# PCB.net
KiCad netlist of a schematic drawn in EAGLE
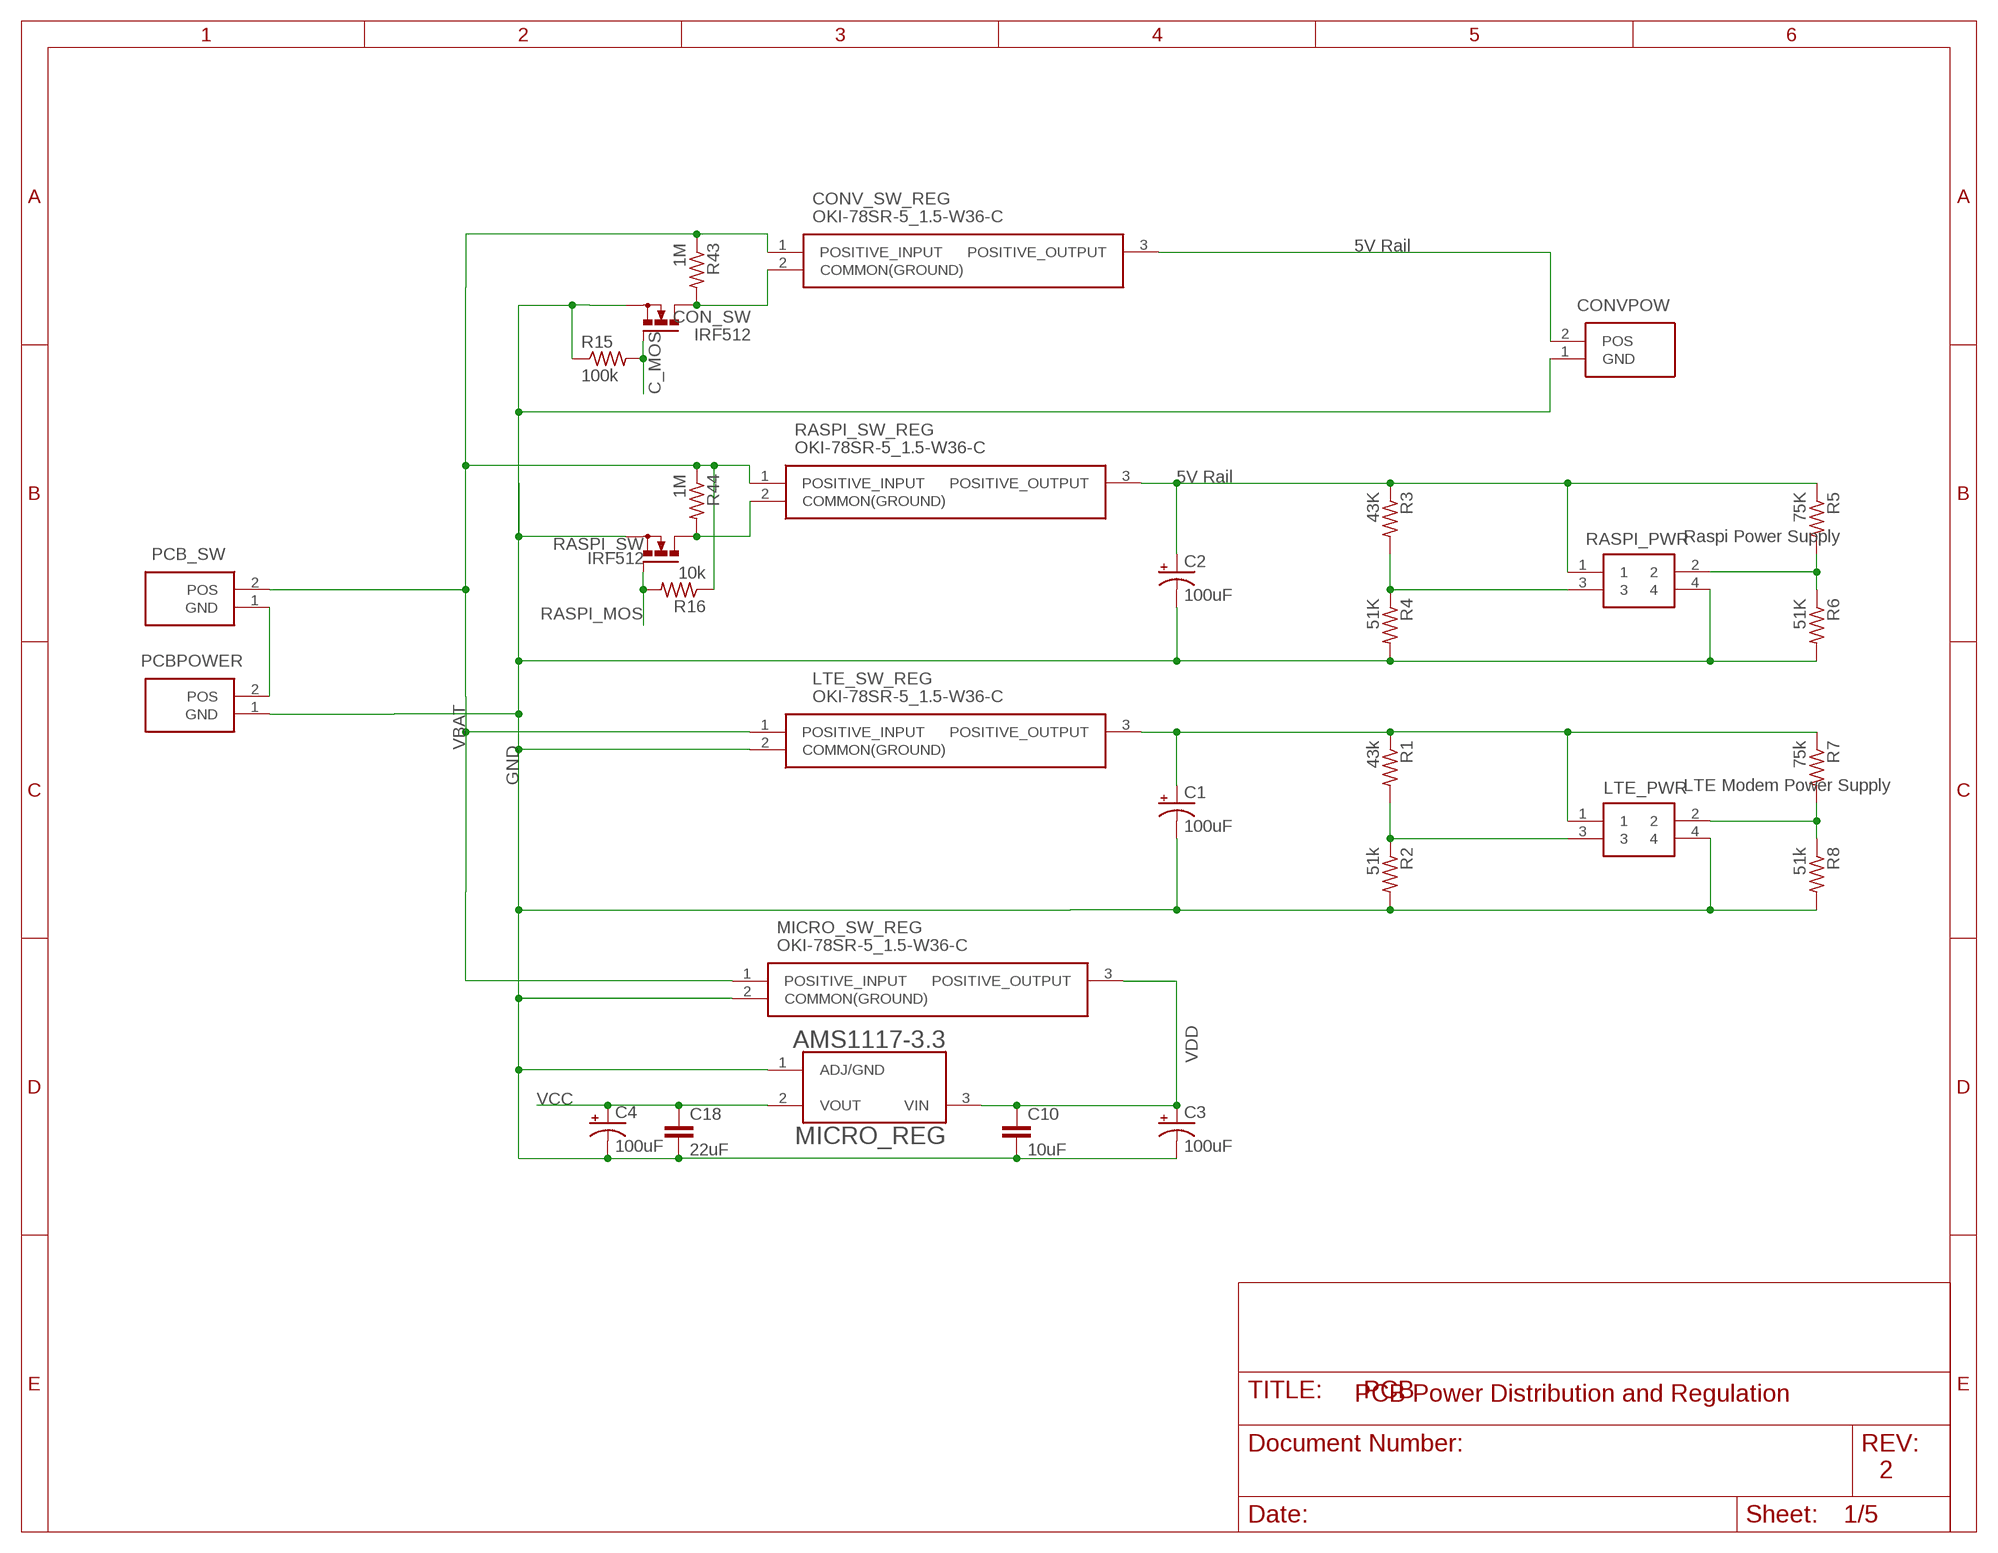
[diagram p0: schematic, sheet 1]
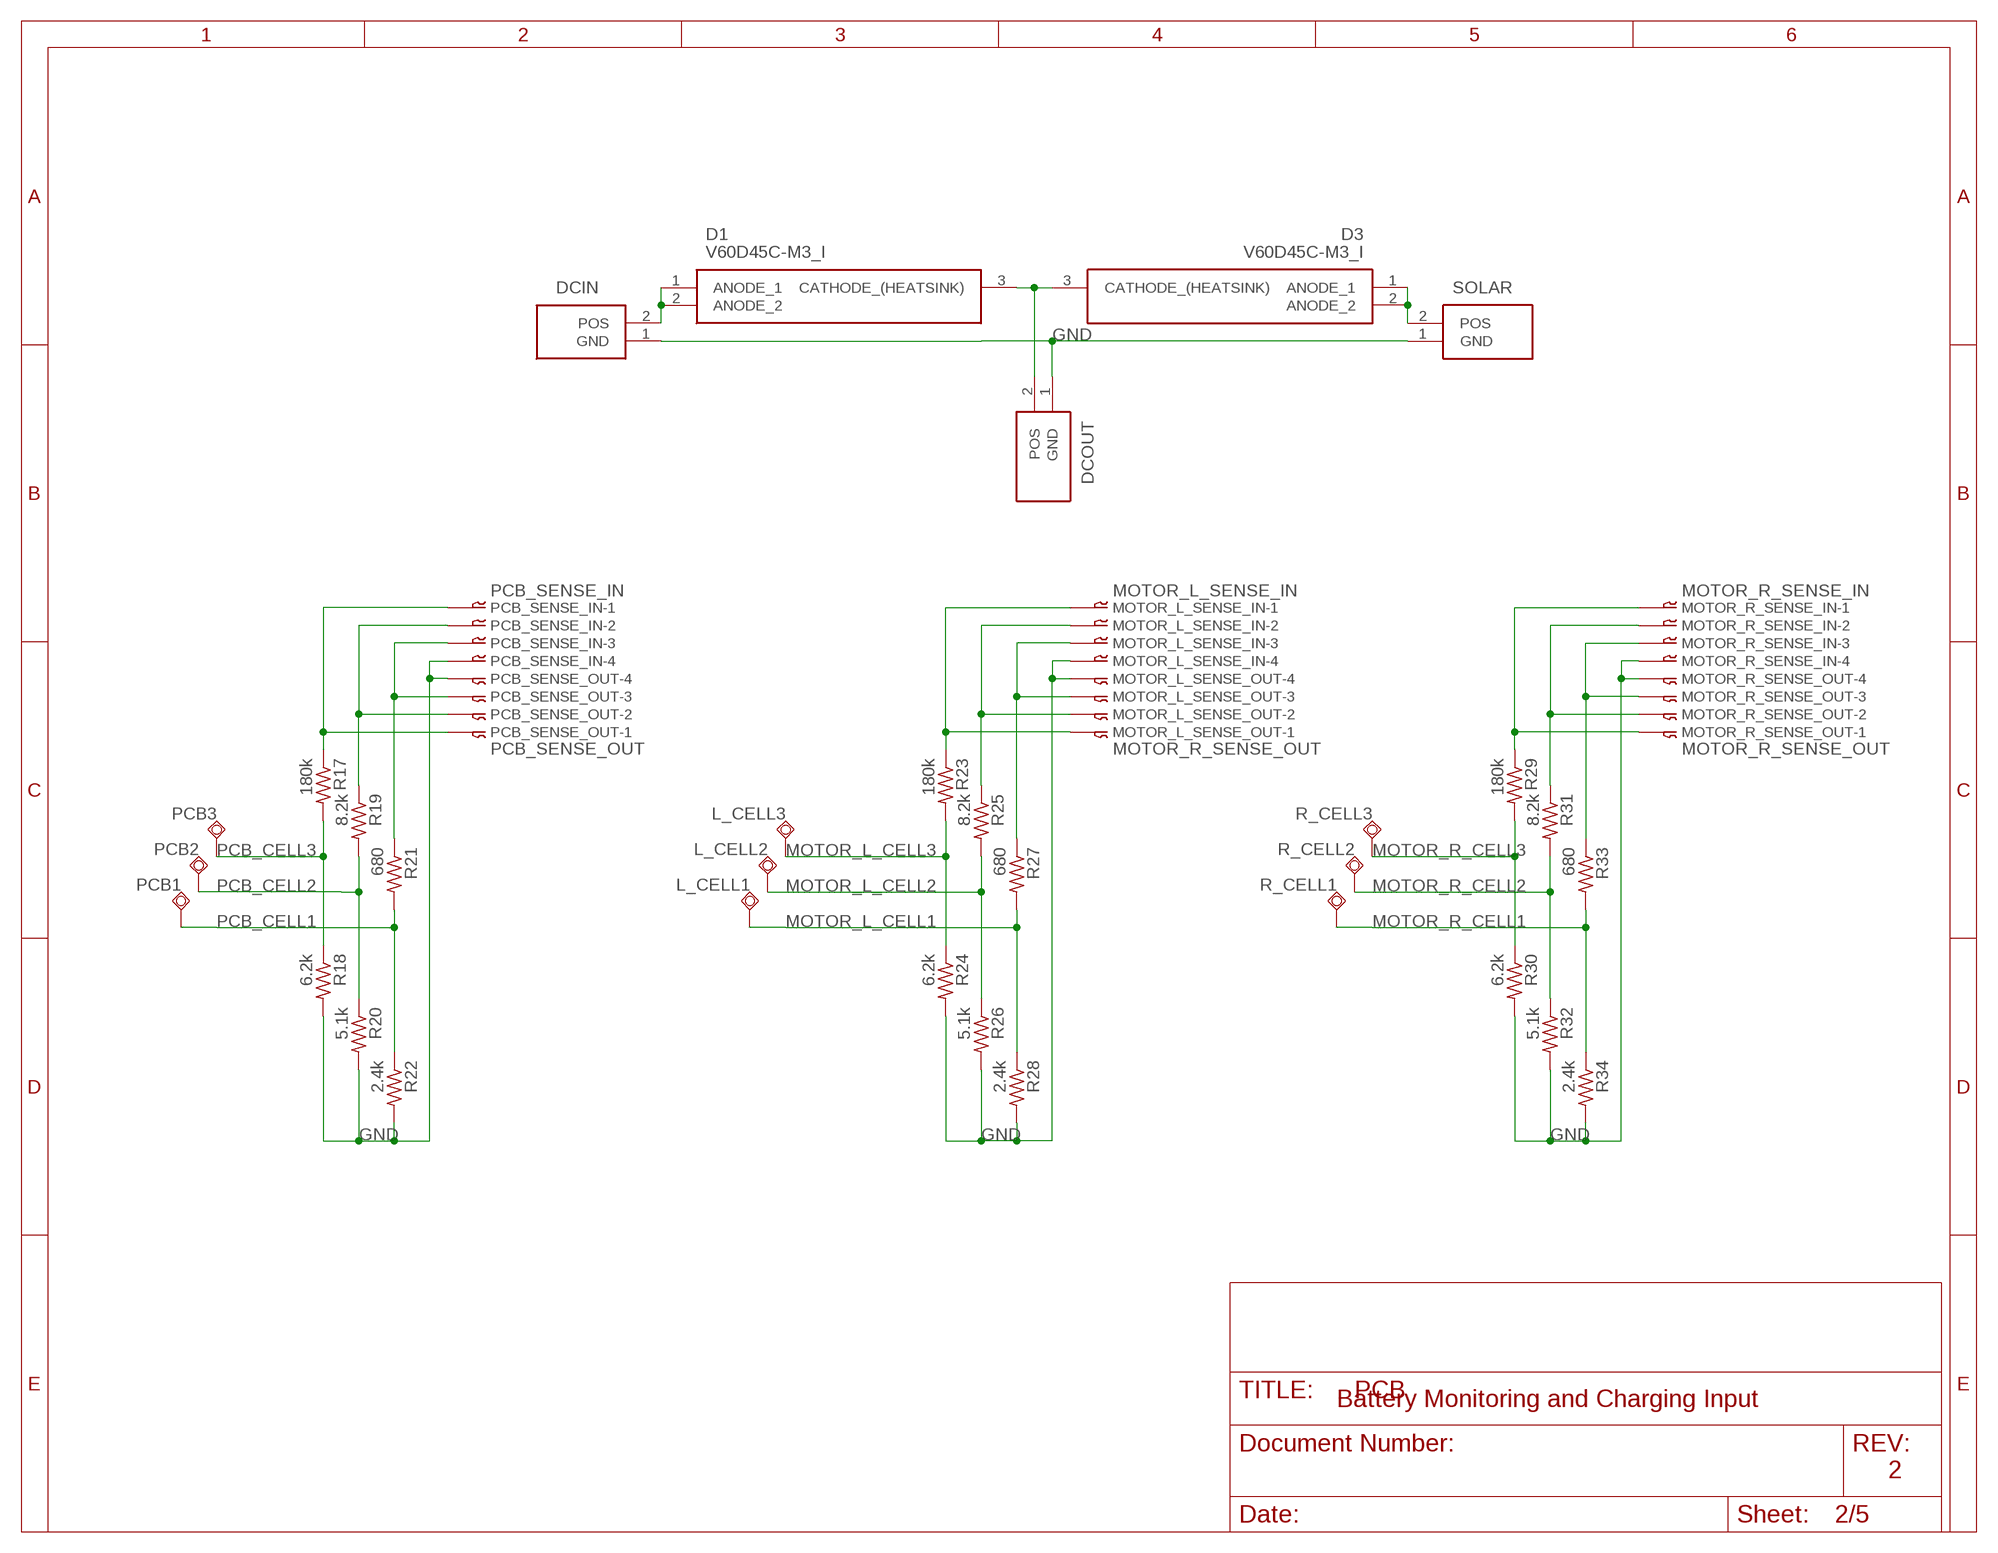
[diagram p1: schematic, sheet 2]
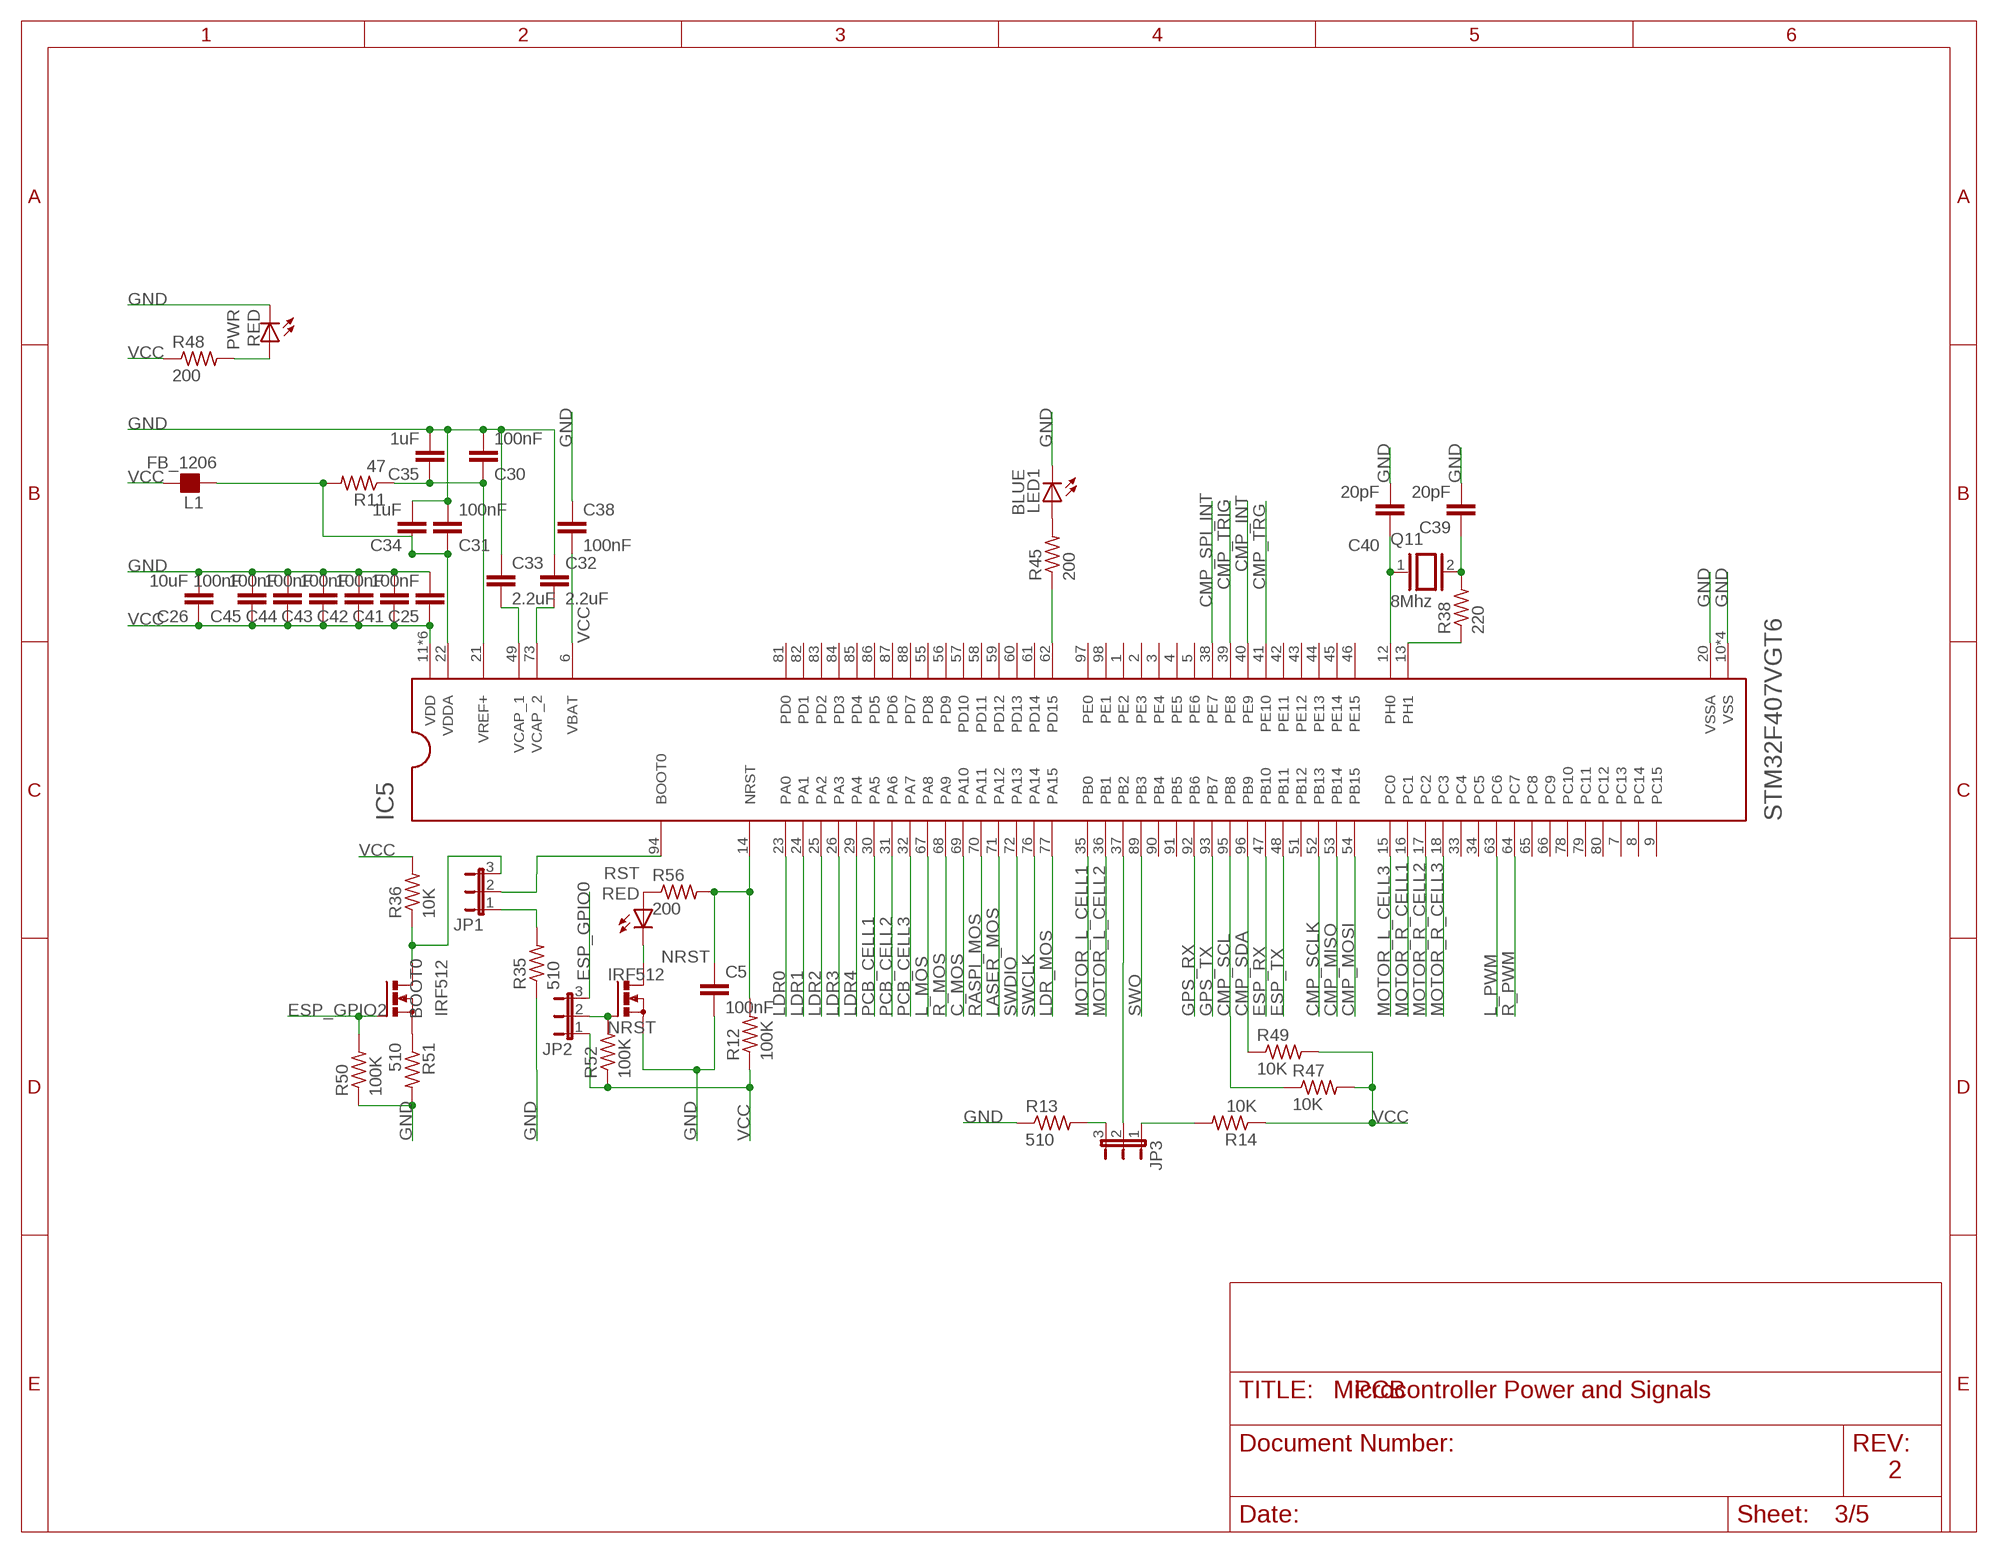
[diagram p2: schematic, sheet 3]
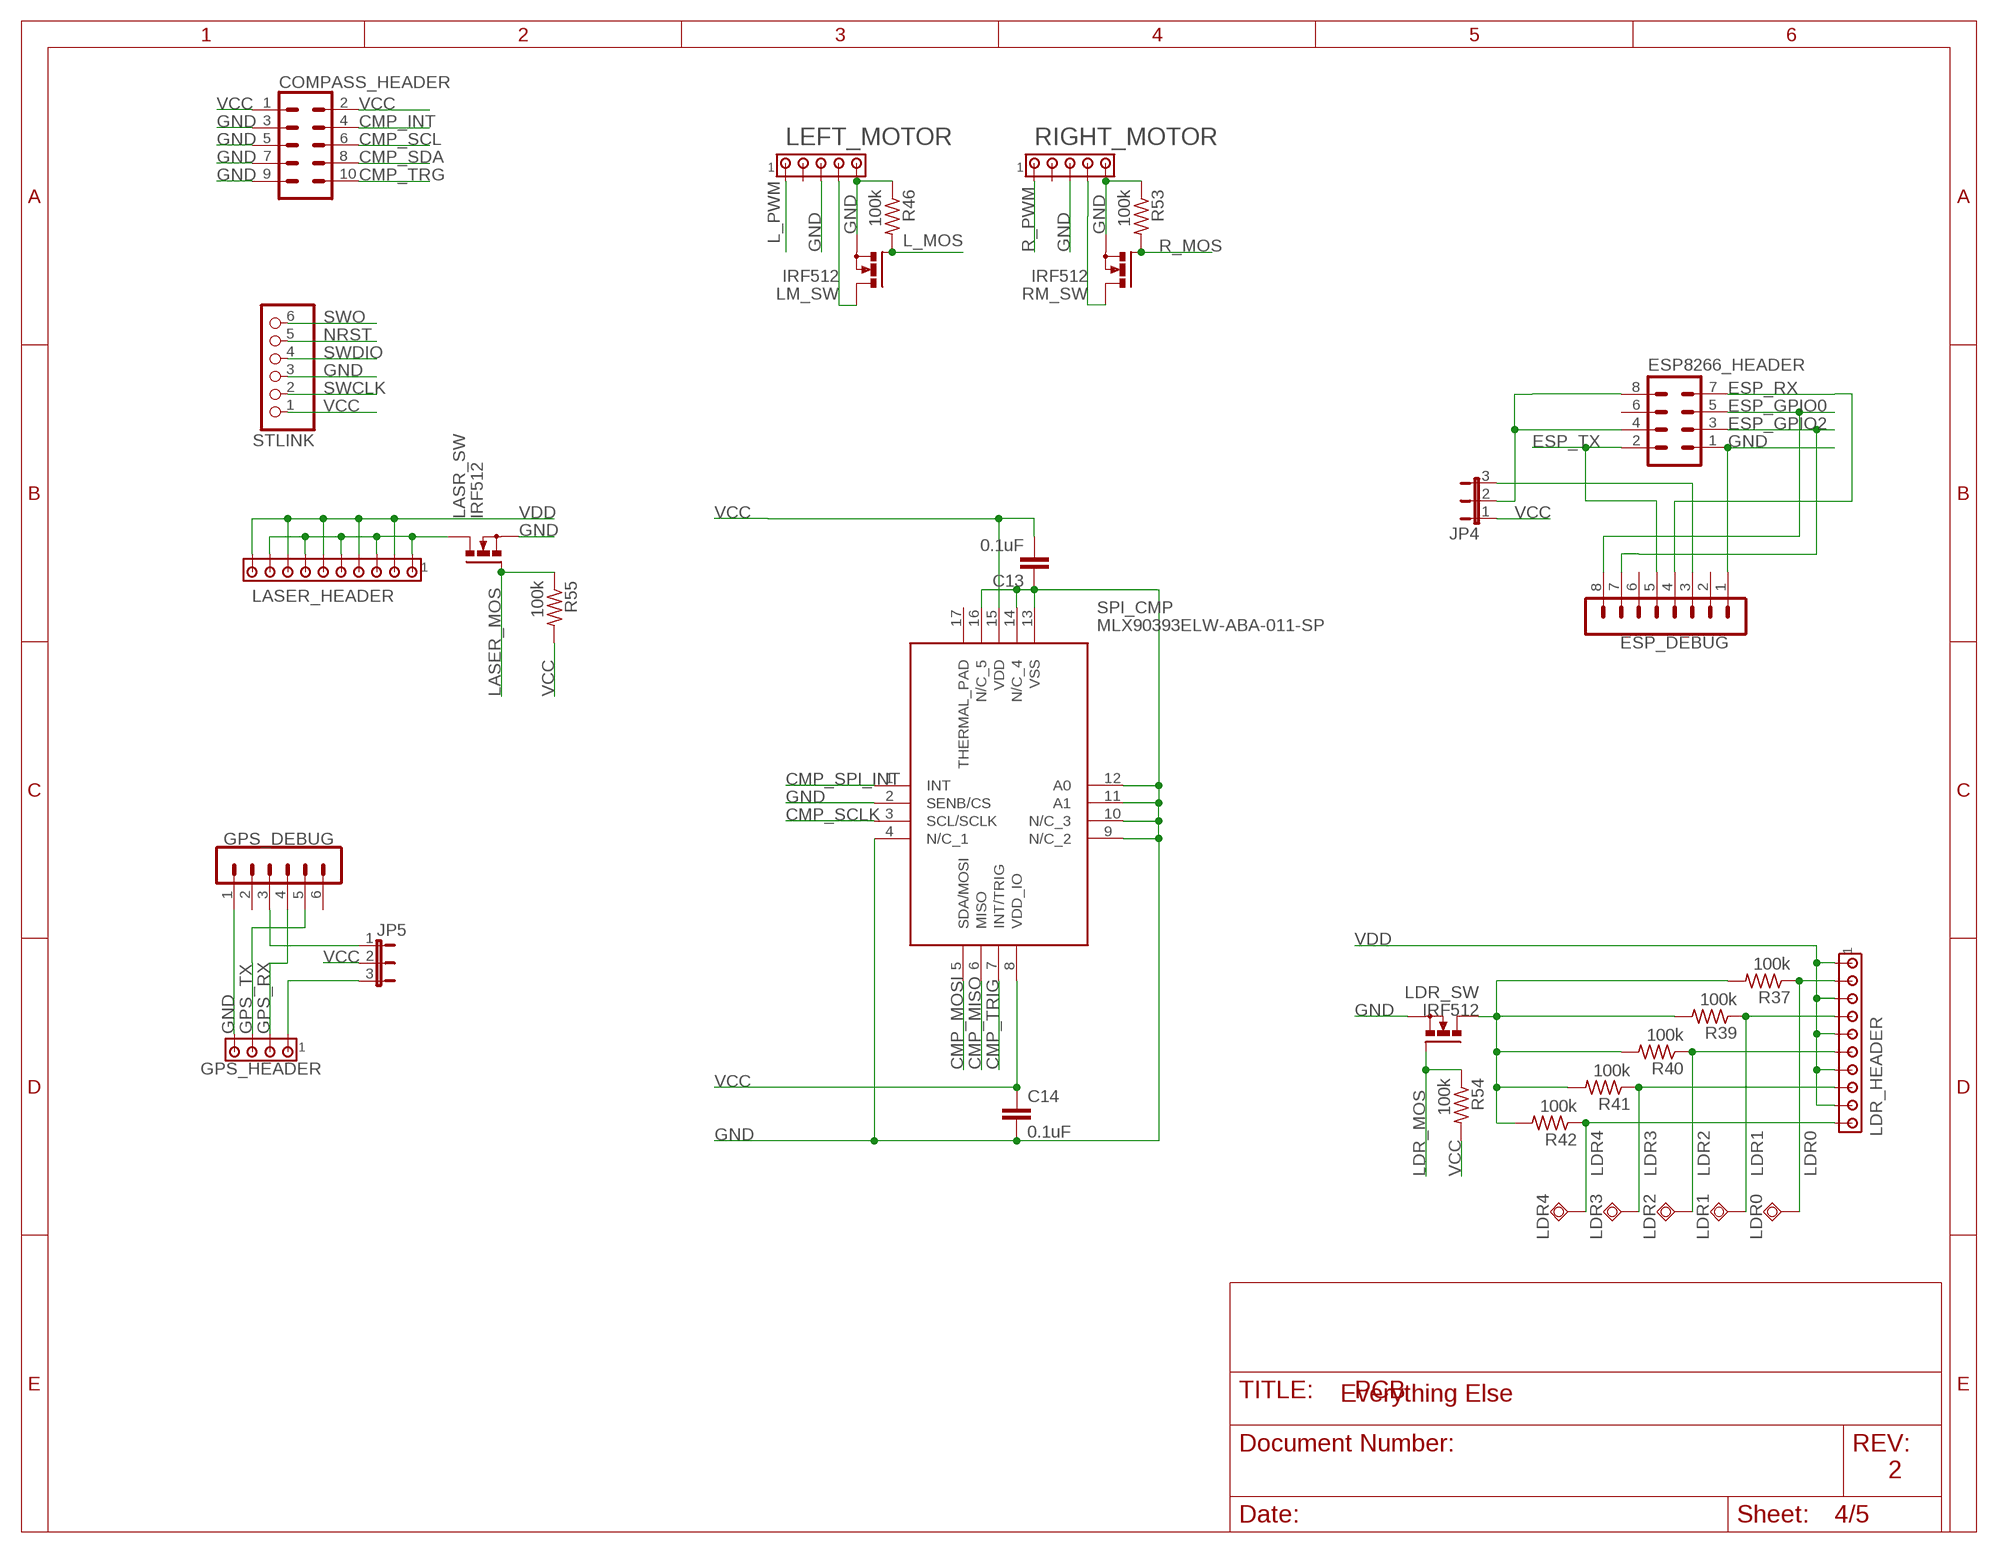
[diagram p3: schematic, sheet 4]
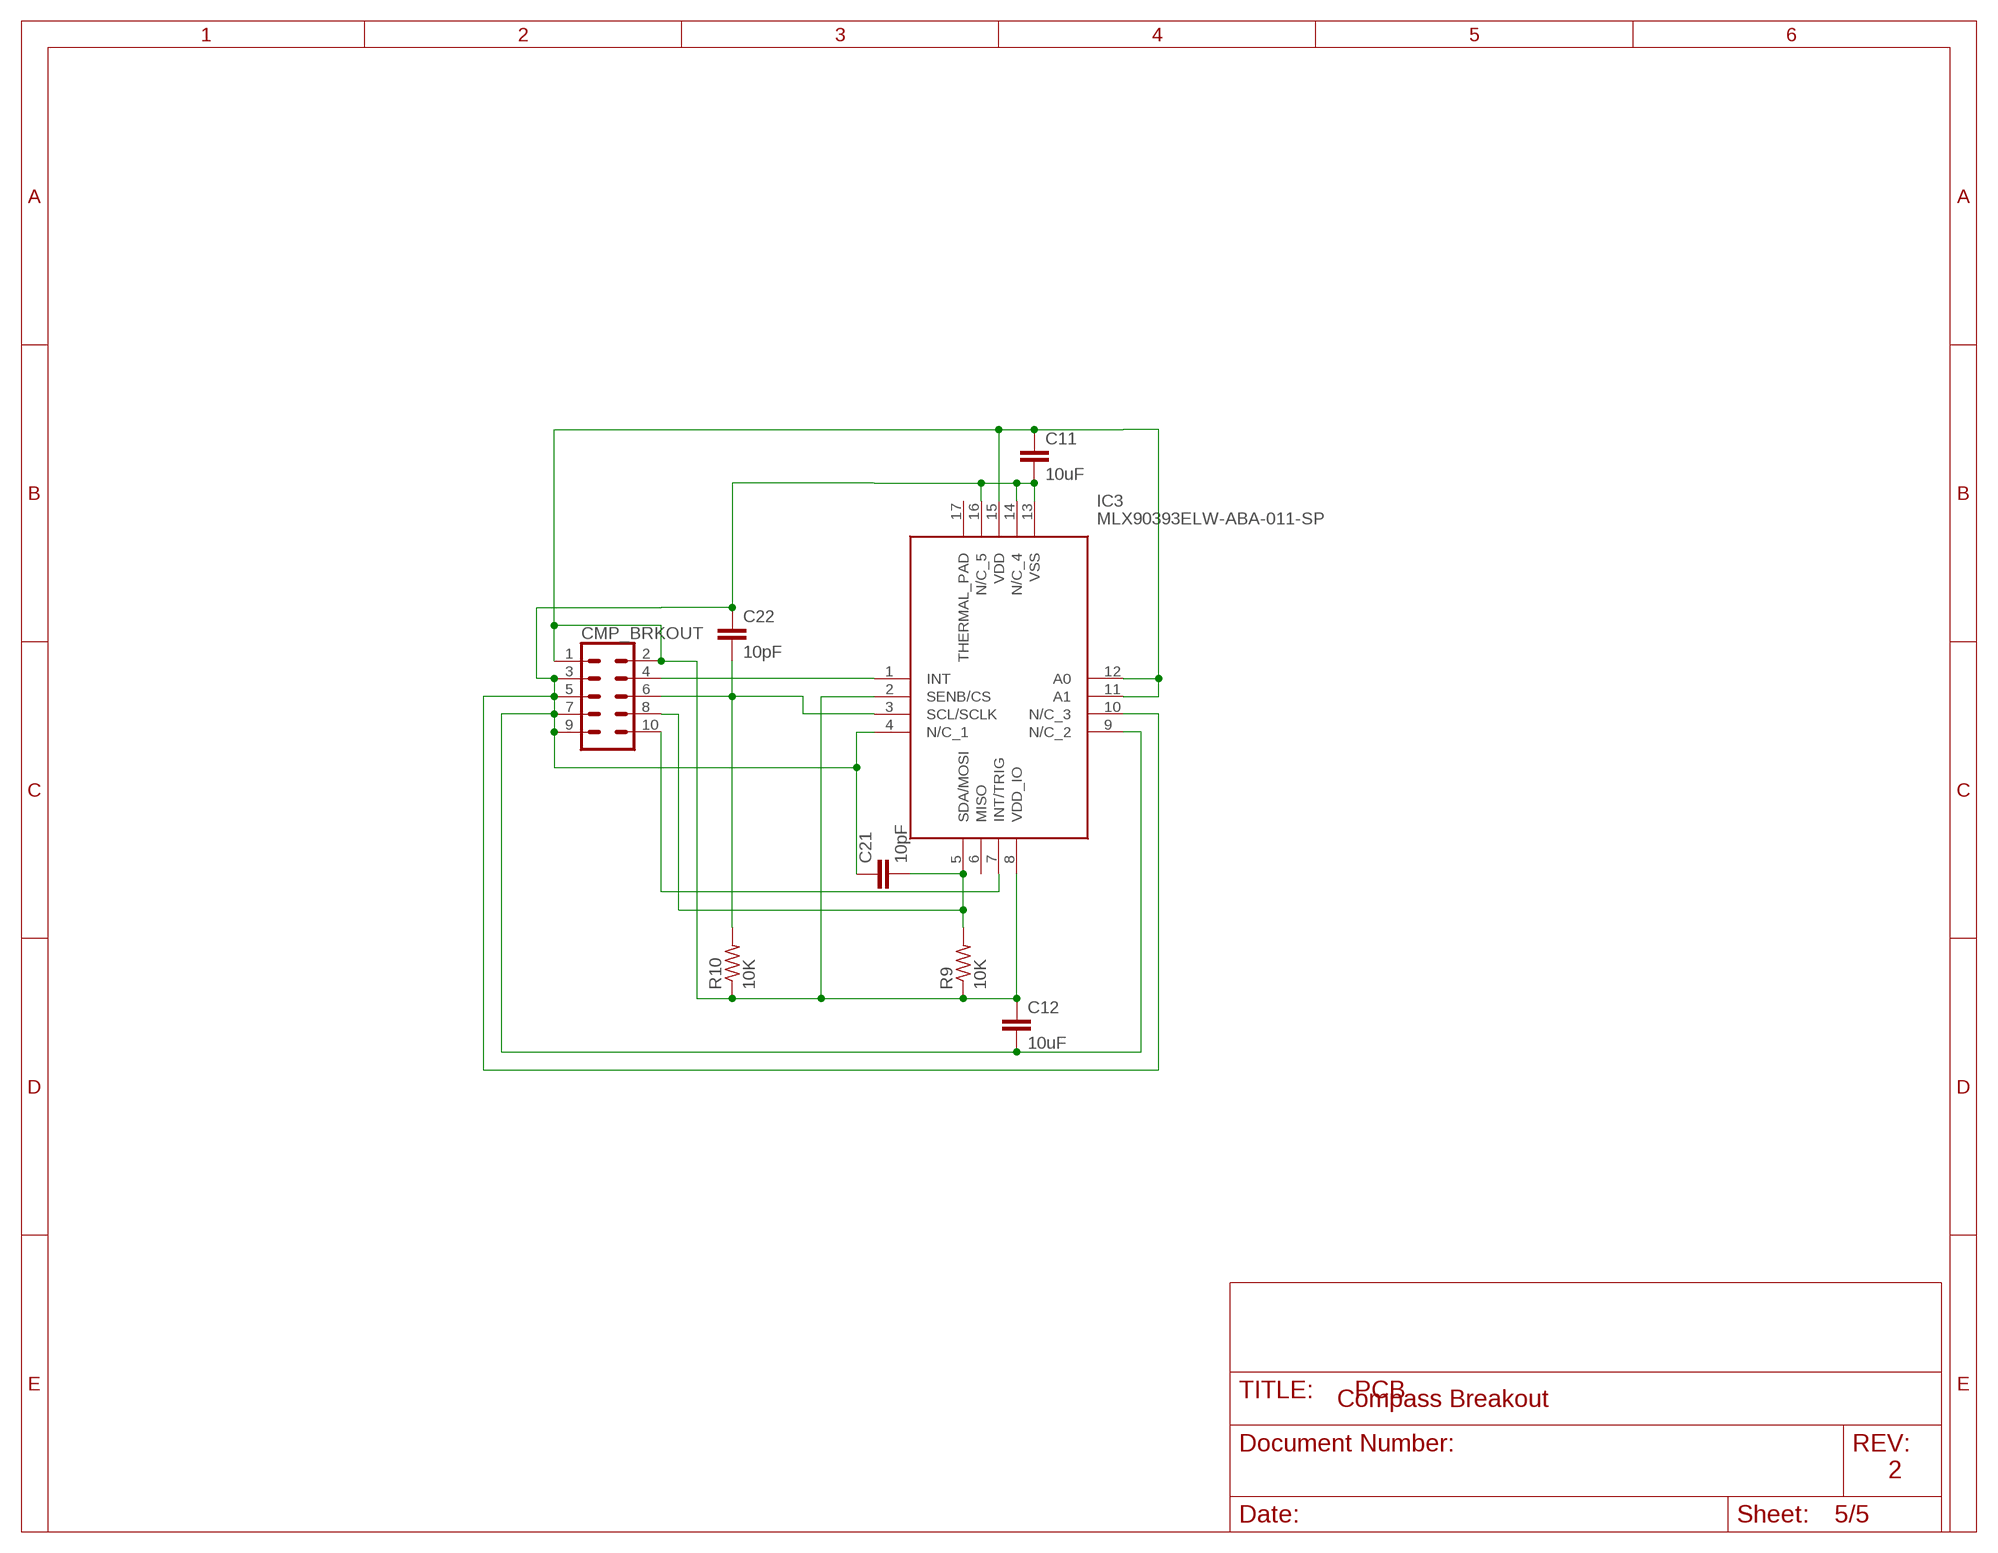
[diagram p4: schematic, sheet 5]

(export (version "E")
  (design (tool "Eeschema 10.0.6"))
  (components
    (comp (ref "C1")
      (value "100uF")
      (footprint "eagle-import:140CLH-0810")
      (libsource (lib "eagle-import") (part "CPOL-US140CLH-0810"))
    )
    (comp (ref "C2")
      (value "100uF")
      (footprint "eagle-import:140CLH-0810")
      (libsource (lib "eagle-import") (part "CPOL-US140CLH-0810"))
    )
    (comp (ref "C3")
      (value "100uF")
      (footprint "eagle-import:140CLH-0810")
      (libsource (lib "eagle-import") (part "CPOL-US140CLH-0810"))
    )
    (comp (ref "C4")
      (value "100uF")
      (footprint "eagle-import:140CLH-0810")
      (libsource (lib "eagle-import") (part "CPOL-US140CLH-0810"))
    )
    (comp (ref "C10")
      (value "10uF")
      (footprint "eagle-import:C0805")
      (libsource (lib "eagle-import") (part "resistor_348_C-EUC0805"))
    )
    (comp (ref "C18")
      (value "22uF")
      (footprint "eagle-import:C0805")
      (libsource (lib "eagle-import") (part "resistor_348_C-EUC0805"))
    )
    (comp (ref "CONVPOW")
      (value "PRT-10474")
      (footprint "eagle-import:SHDR2W320P716_1X2_1574X813X158")
      (libsource (lib "eagle-import") (part "PRT-10474"))
    )
    (comp (ref "CONV_SW_REG")
      (value "OKI-78SR-5_1.5-W36-C")
      (footprint "eagle-import:OKI-78SR")
      (fields
        (field (name "ARROW_PART_NUMBER") "OKI-78SR-5/1.5-W36-C")
        (field (name "RS_PART_NUMBER") "1736928")
      )
      (libsource (lib "eagle-import") (part "OKI-78SR-5_1.5-W36-C"))
    )
    (comp (ref "CON_SW")
      (value "IRF512")
      (footprint "eagle-import:TO220BV")
      (libsource (lib "eagle-import") (part "IRF512"))
    )
    (comp (ref "LTE_PWR")
      (value "LTE Modem Power Supply")
      (footprint "eagle-import:105057-0001")
      (fields (field (name "ARROW_PART_NUMBER") "105057-0001") (field (name "RS_PART_NUMBER") "8967579"))
      (libsource (lib "eagle-import") (part "105057-0001"))
    )
    (comp (ref "LTE_SW_REG")
      (value "OKI-78SR-5_1.5-W36-C")
      (footprint "eagle-import:OKI-78SR")
      (fields
        (field (name "ARROW_PART_NUMBER") "OKI-78SR-5/1.5-W36-C")
        (field (name "RS_PART_NUMBER") "1736928")
      )
      (libsource (lib "eagle-import") (part "OKI-78SR-5_1.5-W36-C"))
    )
    (comp (ref "MICRO_REG")
      (value "AMS1117-3.3")
      (footprint "eagle-import:SOT229P700X180-4N")
      (fields (field (name "MF") "Advanced Monolithic Systems"))
      (libsource (lib "eagle-import") (part "AMS1117-3.3"))
    )
    (comp (ref "MICRO_SW_REG")
      (value "OKI-78SR-5_1.5-W36-C")
      (footprint "eagle-import:OKI-78SR")
      (fields
        (field (name "ARROW_PART_NUMBER") "OKI-78SR-5/1.5-W36-C")
        (field (name "RS_PART_NUMBER") "1736928")
      )
      (libsource (lib "eagle-import") (part "OKI-78SR-5_1.5-W36-C"))
    )
    (comp (ref "PCBPOWER")
      (value "PRT-10474")
      (footprint "eagle-import:SHDR2W320P716_1X2_1574X813X158")
      (libsource (lib "eagle-import") (part "PRT-10474"))
    )
    (comp (ref "PCB_SW")
      (value "PRT-10474")
      (footprint "eagle-import:SHDR2W320P716_1X2_1574X813X158")
      (libsource (lib "eagle-import") (part "PRT-10474"))
    )
    (comp (ref "R1")
      (value "43k")
      (footprint "eagle-import:R0805")
      (libsource (lib "eagle-import") (part "resistor_348_R-US_R0805"))
    )
    (comp (ref "R2")
      (value "51k")
      (footprint "eagle-import:R0805")
      (libsource (lib "eagle-import") (part "resistor_348_R-US_R0805"))
    )
    (comp (ref "R3")
      (value "43K")
      (footprint "eagle-import:R0805")
      (libsource (lib "eagle-import") (part "resistor_348_R-US_R0805"))
    )
    (comp (ref "R4")
      (value "51K")
      (footprint "eagle-import:R0805")
      (libsource (lib "eagle-import") (part "resistor_348_R-US_R0805"))
    )
    (comp (ref "R5")
      (value "75K")
      (footprint "eagle-import:R0805")
      (libsource (lib "eagle-import") (part "resistor_348_R-US_R0805"))
    )
    (comp (ref "R6")
      (value "51K")
      (footprint "eagle-import:R0805")
      (libsource (lib "eagle-import") (part "resistor_348_R-US_R0805"))
    )
    (comp (ref "R7")
      (value "75k")
      (footprint "eagle-import:R0805")
      (libsource (lib "eagle-import") (part "resistor_348_R-US_R0805"))
    )
    (comp (ref "R8")
      (value "51k")
      (footprint "eagle-import:R0805")
      (libsource (lib "eagle-import") (part "resistor_348_R-US_R0805"))
    )
    (comp (ref "R15")
      (value "100k")
      (footprint "eagle-import:R0805")
      (libsource (lib "eagle-import") (part "resistor_348_R-US_R0805"))
    )
    (comp (ref "R16")
      (value "10k")
      (footprint "eagle-import:R0805")
      (libsource (lib "eagle-import") (part "resistor_348_R-US_R0805"))
    )
    (comp (ref "R43")
      (value "1M")
      (footprint "eagle-import:R0805")
      (libsource (lib "eagle-import") (part "resistor_348_R-US_R0805"))
    )
    (comp (ref "R44")
      (value "1M")
      (footprint "eagle-import:R0805")
      (libsource (lib "eagle-import") (part "resistor_348_R-US_R0805"))
    )
    (comp (ref "RASPI_PWR")
      (value "Raspi Power Supply")
      (footprint "eagle-import:105057-0001")
      (fields (field (name "ARROW_PART_NUMBER") "105057-0001") (field (name "RS_PART_NUMBER") "8967579"))
      (libsource (lib "eagle-import") (part "105057-0001"))
    )
    (comp (ref "RASPI_SW")
      (value "IRF512")
      (footprint "eagle-import:TO220BV")
      (libsource (lib "eagle-import") (part "IRF512"))
    )
    (comp (ref "RASPI_SW_REG")
      (value "OKI-78SR-5_1.5-W36-C")
      (footprint "eagle-import:OKI-78SR")
      (fields
        (field (name "ARROW_PART_NUMBER") "OKI-78SR-5/1.5-W36-C")
        (field (name "RS_PART_NUMBER") "1736928")
      )
      (libsource (lib "eagle-import") (part "OKI-78SR-5_1.5-W36-C"))
    )
    (comp (ref "D1")
      (value "V60D45C-M3_I")
      (footprint "eagle-import:TO-263AC(SMPD)")
      (fields (field (name "ARROW_PART_NUMBER") "V60D45C-M3/I") (field (name "RS_PART_NUMBER") "8321024"))
      (libsource (lib "eagle-import") (part "V60D45C-M3_I"))
    )
    (comp (ref "D3")
      (value "V60D45C-M3_I")
      (footprint "eagle-import:TO-263AC(SMPD)")
      (fields (field (name "ARROW_PART_NUMBER") "V60D45C-M3/I") (field (name "RS_PART_NUMBER") "8321024"))
      (libsource (lib "eagle-import") (part "V60D45C-M3_I"))
    )
    (comp (ref "DCIN")
      (value "PRT-10474")
      (footprint "eagle-import:SHDR2W320P716_1X2_1574X813X158")
      (libsource (lib "eagle-import") (part "PRT-10474"))
    )
    (comp (ref "DCOUT")
      (value "PRT-10474")
      (footprint "eagle-import:SHDR2W320P716_1X2_1574X813X158")
      (libsource (lib "eagle-import") (part "PRT-10474"))
    )
    (comp (ref "L_CELL1")
      (value "TPSQB2,54")
      (footprint "eagle-import:B2,54")
      (libsource (lib "eagle-import") (part "TPSQB2,54"))
    )
    (comp (ref "L_CELL2")
      (value "TPSQB2,54")
      (footprint "eagle-import:B2,54")
      (libsource (lib "eagle-import") (part "TPSQB2,54"))
    )
    (comp (ref "L_CELL3")
      (value "PCB_CELL3")
      (footprint "eagle-import:B2,54")
      (libsource (lib "eagle-import") (part "TPSQB2,54"))
    )
    (comp (ref "MOTOR_L_SENSE_IN")
      (value "MOTOR_L_SENSE_IN")
      (footprint "eagle-import:B4B-XH")
      (libsource (lib "eagle-import") (part "04-JST-B4B-XH-A"))
    )
    (comp (ref "MOTOR_L_SENSE_OUT")
      (value "MOTOR_R_SENSE_OUT")
      (footprint "eagle-import:B4B-XH")
      (libsource (lib "eagle-import") (part "04-JST-B4B-XH-A"))
    )
    (comp (ref "MOTOR_R_SENSE_IN")
      (value "MOTOR_R_SENSE_IN")
      (footprint "eagle-import:B4B-XH")
      (libsource (lib "eagle-import") (part "04-JST-B4B-XH-A"))
    )
    (comp (ref "MOTOR_R_SENSE_OUT")
      (value "MOTOR_R_SENSE_OUT")
      (footprint "eagle-import:B4B-XH")
      (libsource (lib "eagle-import") (part "04-JST-B4B-XH-A"))
    )
    (comp (ref "PCB1")
      (value "TPSQB2,54")
      (footprint "eagle-import:B2,54")
      (libsource (lib "eagle-import") (part "TPSQB2,54"))
    )
    (comp (ref "PCB2")
      (value "TPSQB2,54")
      (footprint "eagle-import:B2,54")
      (libsource (lib "eagle-import") (part "TPSQB2,54"))
    )
    (comp (ref "PCB3")
      (value "PCB_CELL3")
      (footprint "eagle-import:B2,54")
      (libsource (lib "eagle-import") (part "TPSQB2,54"))
    )
    (comp (ref "PCB_SENSE_IN")
      (value "PCB_SENSE_IN")
      (footprint "eagle-import:B4B-XH")
      (libsource (lib "eagle-import") (part "04-JST-B4B-XH-A"))
    )
    (comp (ref "PCB_SENSE_OUT")
      (value "PCB_SENSE_OUT")
      (footprint "eagle-import:B4B-XH")
      (libsource (lib "eagle-import") (part "04-JST-B4B-XH-A"))
    )
    (comp (ref "R17")
      (value "180k")
      (footprint "eagle-import:R0805")
      (libsource (lib "eagle-import") (part "resistor_348_R-US_R0805"))
    )
    (comp (ref "R18")
      (value "6.2k")
      (footprint "eagle-import:R0805")
      (libsource (lib "eagle-import") (part "resistor_348_R-US_R0805"))
    )
    (comp (ref "R19")
      (value "8.2k")
      (footprint "eagle-import:R0805")
      (libsource (lib "eagle-import") (part "resistor_348_R-US_R0805"))
    )
    (comp (ref "R20")
      (value "5.1k")
      (footprint "eagle-import:R0805")
      (libsource (lib "eagle-import") (part "resistor_348_R-US_R0805"))
    )
    (comp (ref "R21")
      (value "680")
      (footprint "eagle-import:R0805")
      (libsource (lib "eagle-import") (part "resistor_348_R-US_R0805"))
    )
    (comp (ref "R22")
      (value "2.4k")
      (footprint "eagle-import:R0805")
      (libsource (lib "eagle-import") (part "resistor_348_R-US_R0805"))
    )
    (comp (ref "R23")
      (value "180k")
      (footprint "eagle-import:R0805")
      (libsource (lib "eagle-import") (part "resistor_348_R-US_R0805"))
    )
    (comp (ref "R24")
      (value "6.2k")
      (footprint "eagle-import:R0805")
      (libsource (lib "eagle-import") (part "resistor_348_R-US_R0805"))
    )
    (comp (ref "R25")
      (value "8.2k")
      (footprint "eagle-import:R0805")
      (libsource (lib "eagle-import") (part "resistor_348_R-US_R0805"))
    )
    (comp (ref "R26")
      (value "5.1k")
      (footprint "eagle-import:R0805")
      (libsource (lib "eagle-import") (part "resistor_348_R-US_R0805"))
    )
    (comp (ref "R27")
      (value "680")
      (footprint "eagle-import:R0805")
      (libsource (lib "eagle-import") (part "resistor_348_R-US_R0805"))
    )
    (comp (ref "R28")
      (value "2.4k")
      (footprint "eagle-import:R0805")
      (libsource (lib "eagle-import") (part "resistor_348_R-US_R0805"))
    )
    (comp (ref "R29")
      (value "180k")
      (footprint "eagle-import:R0805")
      (libsource (lib "eagle-import") (part "resistor_348_R-US_R0805"))
    )
    (comp (ref "R30")
      (value "6.2k")
      (footprint "eagle-import:R0805")
      (libsource (lib "eagle-import") (part "resistor_348_R-US_R0805"))
    )
    (comp (ref "R31")
      (value "8.2k")
      (footprint "eagle-import:R0805")
      (libsource (lib "eagle-import") (part "resistor_348_R-US_R0805"))
    )
    (comp (ref "R32")
      (value "5.1k")
      (footprint "eagle-import:R0805")
      (libsource (lib "eagle-import") (part "resistor_348_R-US_R0805"))
    )
    (comp (ref "R33")
      (value "680")
      (footprint "eagle-import:R0805")
      (libsource (lib "eagle-import") (part "resistor_348_R-US_R0805"))
    )
    (comp (ref "R34")
      (value "2.4k")
      (footprint "eagle-import:R0805")
      (libsource (lib "eagle-import") (part "resistor_348_R-US_R0805"))
    )
    (comp (ref "R_CELL1")
      (value "TPSQB2,54")
      (footprint "eagle-import:B2,54")
      (libsource (lib "eagle-import") (part "TPSQB2,54"))
    )
    (comp (ref "R_CELL2")
      (value "TPSQB2,54")
      (footprint "eagle-import:B2,54")
      (libsource (lib "eagle-import") (part "TPSQB2,54"))
    )
    (comp (ref "R_CELL3")
      (value "PCB_CELL3")
      (footprint "eagle-import:B2,54")
      (libsource (lib "eagle-import") (part "TPSQB2,54"))
    )
    (comp (ref "SOLAR")
      (value "PRT-10474")
      (footprint "eagle-import:SHDR2W320P716_1X2_1574X813X158")
      (libsource (lib "eagle-import") (part "PRT-10474"))
    )
    (comp (ref "C13")
      (value "0.1uF")
      (footprint "eagle-import:C1206")
      (libsource (lib "eagle-import") (part "resistor_348_C-EUC1206"))
    )
    (comp (ref "C14")
      (value "0.1uF")
      (footprint "eagle-import:C1206")
      (libsource (lib "eagle-import") (part "resistor_348_C-EUC1206"))
    )
    (comp (ref "COMPASS_HEADER")
      (value "CONN_05X2SHD")
      (footprint "eagle-import:2X5-SHROUDED")
      (libsource (lib "eagle-import") (part "CONN_05X2SHD"))
    )
    (comp (ref "ESP8266_HEADER")
      (value "MA04-2")
      (footprint "eagle-import:MA04-2")
      (libsource (lib "eagle-import") (part "MA04-2"))
    )
    (comp (ref "ESP_DEBUG")
      (value "MA08-1")
      (footprint "eagle-import:MA08-1")
      (libsource (lib "eagle-import") (part "MA08-1"))
    )
    (comp (ref "GPS_DEBUG")
      (value "MA06-1")
      (footprint "eagle-import:MA06-1")
      (libsource (lib "eagle-import") (part "MA06-1"))
    )
    (comp (ref "GPS_HEADER")
      (value "MTA04-100")
      (footprint "eagle-import:10X04MTA")
      (libsource (lib "eagle-import") (part "MTA04-100"))
    )
    (comp (ref "JP4")
      (value "JP2E")
      (footprint "eagle-import:JP2")
      (libsource (lib "eagle-import") (part "JP2E"))
    )
    (comp (ref "JP5")
      (value "JP2E")
      (footprint "eagle-import:JP2")
      (libsource (lib "eagle-import") (part "JP2E"))
    )
    (comp (ref "LASER_HEADER")
      (value "MTA10-100")
      (footprint "eagle-import:10X10MTA")
      (libsource (lib "eagle-import") (part "MTA10-100"))
    )
    (comp (ref "LASR_SW")
      (value "IRF512")
      (footprint "eagle-import:TO220BV")
      (libsource (lib "eagle-import") (part "IRF512"))
    )
    (comp (ref "LDR0")
      (value "TPSQB2,54")
      (footprint "eagle-import:B2,54")
      (libsource (lib "eagle-import") (part "TPSQB2,54"))
    )
    (comp (ref "LDR1")
      (value "TPSQB2,54")
      (footprint "eagle-import:B2,54")
      (libsource (lib "eagle-import") (part "TPSQB2,54"))
    )
    (comp (ref "LDR2")
      (value "TPSQB2,54")
      (footprint "eagle-import:B2,54")
      (libsource (lib "eagle-import") (part "TPSQB2,54"))
    )
    (comp (ref "LDR3")
      (value "TPSQB2,54")
      (footprint "eagle-import:B2,54")
      (libsource (lib "eagle-import") (part "TPSQB2,54"))
    )
    (comp (ref "LDR4")
      (value "TPSQB2,54")
      (footprint "eagle-import:B2,54")
      (libsource (lib "eagle-import") (part "TPSQB2,54"))
    )
    (comp (ref "LDR_HEADER")
      (value "MTA10-100")
      (footprint "eagle-import:10X10MTA")
      (libsource (lib "eagle-import") (part "MTA10-100"))
    )
    (comp (ref "LDR_SW")
      (value "IRF512")
      (footprint "eagle-import:TO220BV")
      (libsource (lib "eagle-import") (part "IRF512"))
    )
    (comp (ref "LEFT_MOTOR")
      (value "MTA05-100")
      (footprint "eagle-import:1X05MTA")
      (libsource (lib "eagle-import") (part "MTA05-100"))
    )
    (comp (ref "LM_SW")
      (value "IRF512")
      (footprint "eagle-import:TO220BV")
      (libsource (lib "eagle-import") (part "IRF512"))
    )
    (comp (ref "R37")
      (value "100k")
      (footprint "eagle-import:R1206")
      (libsource (lib "eagle-import") (part "resistor_348_R-US_R1206"))
    )
    (comp (ref "R39")
      (value "100k")
      (footprint "eagle-import:R1206")
      (libsource (lib "eagle-import") (part "resistor_348_R-US_R1206"))
    )
    (comp (ref "R40")
      (value "100k")
      (footprint "eagle-import:R1206")
      (libsource (lib "eagle-import") (part "resistor_348_R-US_R1206"))
    )
    (comp (ref "R41")
      (value "100k")
      (footprint "eagle-import:R1206")
      (libsource (lib "eagle-import") (part "resistor_348_R-US_R1206"))
    )
    (comp (ref "R42")
      (value "100k")
      (footprint "eagle-import:R1206")
      (libsource (lib "eagle-import") (part "resistor_348_R-US_R1206"))
    )
    (comp (ref "R46")
      (value "100k")
      (footprint "eagle-import:R1206")
      (libsource (lib "eagle-import") (part "resistor_348_R-US_R1206"))
    )
    (comp (ref "R53")
      (value "100k")
      (footprint "eagle-import:R1206")
      (libsource (lib "eagle-import") (part "resistor_348_R-US_R1206"))
    )
    (comp (ref "R54")
      (value "100k")
      (footprint "eagle-import:R1206")
      (libsource (lib "eagle-import") (part "resistor_348_R-US_R1206"))
    )
    (comp (ref "R55")
      (value "100k")
      (footprint "eagle-import:R1206")
      (libsource (lib "eagle-import") (part "resistor_348_R-US_R1206"))
    )
    (comp (ref "RIGHT_MOTOR")
      (value "MTA05-100")
      (footprint "eagle-import:1X05MTA")
      (libsource (lib "eagle-import") (part "MTA05-100"))
    )
    (comp (ref "RM_SW")
      (value "IRF512")
      (footprint "eagle-import:TO220BV")
      (libsource (lib "eagle-import") (part "IRF512"))
    )
    (comp (ref "SPI_CMP")
      (value "MLX90393ELW-ABA-011-SP")
      (footprint "eagle-import:QFN50P300X300X100-17N")
      (libsource (lib "eagle-import") (part "MLX90393ELW-ABA-011-SP"))
    )
    (comp (ref "STLINK")
      (value "PINHD-1X6")
      (footprint "eagle-import:1X06")
      (libsource (lib "eagle-import") (part "PINHD-1X6"))
    )
    (comp (ref "BOOT0")
      (value "IRF512")
      (footprint "eagle-import:TO220BV")
      (libsource (lib "eagle-import") (part "IRF512"))
    )
    (comp (ref "C5")
      (value "100nF")
      (footprint "eagle-import:C0805")
      (libsource (lib "eagle-import") (part "C-EUC0805"))
    )
    (comp (ref "C25")
      (value "100nF")
      (footprint "eagle-import:C0805")
      (libsource (lib "eagle-import") (part "C-EUC0805"))
    )
    (comp (ref "C26")
      (value "10uF")
      (footprint "eagle-import:C0805")
      (libsource (lib "eagle-import") (part "C-EUC0805"))
    )
    (comp (ref "C30")
      (value "100nF")
      (footprint "eagle-import:C0805")
      (libsource (lib "eagle-import") (part "C-EUC0805"))
    )
    (comp (ref "C31")
      (value "100nF")
      (footprint "eagle-import:C0805")
      (libsource (lib "eagle-import") (part "C-EUC0805"))
    )
    (comp (ref "C32")
      (value "2.2uF")
      (footprint "eagle-import:C0805")
      (libsource (lib "eagle-import") (part "C-EUC0805"))
    )
    (comp (ref "C33")
      (value "2.2uF")
      (footprint "eagle-import:C0805")
      (libsource (lib "eagle-import") (part "C-EUC0805"))
    )
    (comp (ref "C34")
      (value "1uF")
      (footprint "eagle-import:C0805")
      (libsource (lib "eagle-import") (part "C-EUC0805"))
    )
    (comp (ref "C35")
      (value "1uF")
      (footprint "eagle-import:C0805")
      (libsource (lib "eagle-import") (part "C-EUC0805"))
    )
    (comp (ref "C38")
      (value "100nF")
      (footprint "eagle-import:C0805")
      (libsource (lib "eagle-import") (part "C-EUC0805"))
    )
    (comp (ref "C39")
      (value "20pF")
      (footprint "eagle-import:C0805")
      (libsource (lib "eagle-import") (part "C-EUC0805"))
    )
    (comp (ref "C40")
      (value "20pF")
      (footprint "eagle-import:C0805")
      (libsource (lib "eagle-import") (part "C-EUC0805"))
    )
    (comp (ref "C41")
      (value "100nF")
      (footprint "eagle-import:C0805")
      (libsource (lib "eagle-import") (part "C-EUC0805"))
    )
    (comp (ref "C42")
      (value "100nF")
      (footprint "eagle-import:C0805")
      (libsource (lib "eagle-import") (part "C-EUC0805"))
    )
    (comp (ref "C43")
      (value "100nF")
      (footprint "eagle-import:C0805")
      (libsource (lib "eagle-import") (part "C-EUC0805"))
    )
    (comp (ref "C44")
      (value "100nF")
      (footprint "eagle-import:C0805")
      (libsource (lib "eagle-import") (part "C-EUC0805"))
    )
    (comp (ref "C45")
      (value "100nF")
      (footprint "eagle-import:C0805")
      (libsource (lib "eagle-import") (part "C-EUC0805"))
    )
    (comp (ref "IC5")
      (value "STM32F407VGT6")
      (footprint "eagle-import:QFP50P1600X1600X160-100N")
      (fields (field (name "MF") "STMicroelectronics"))
      (libsource (lib "eagle-import") (part "STM32F407VGT6"))
    )
    (comp (ref "JP1")
      (value "JP2E")
      (footprint "eagle-import:JP2")
      (libsource (lib "eagle-import") (part "JP2E"))
    )
    (comp (ref "JP2")
      (value "JP2E")
      (footprint "eagle-import:JP2")
      (libsource (lib "eagle-import") (part "JP2E"))
    )
    (comp (ref "JP3")
      (value "JP2E")
      (footprint "eagle-import:JP2")
      (libsource (lib "eagle-import") (part "JP2E"))
    )
    (comp (ref "L1")
      (value "FB_1206")
      (footprint "eagle-import:L1206")
      (libsource (lib "eagle-import") (part "FB_1206"))
    )
    (comp (ref "LED1")
      (value "BLUE")
      (footprint "eagle-import:CHIPLED_0805")
      (libsource (lib "eagle-import") (part "LEDCHIPLED_0805"))
    )
    (comp (ref "NRST")
      (value "IRF512")
      (footprint "eagle-import:TO220BV")
      (libsource (lib "eagle-import") (part "IRF512"))
    )
    (comp (ref "PWR")
      (value "RED")
      (footprint "eagle-import:CHIPLED_0805")
      (libsource (lib "eagle-import") (part "LEDCHIPLED_0805"))
    )
    (comp (ref "Q11")
      (value "8Mhz")
      (footprint "eagle-import:QS")
      (libsource (lib "eagle-import") (part "XTAL/S"))
    )
    (comp (ref "R11")
      (value "47")
      (footprint "eagle-import:R0805")
      (libsource (lib "eagle-import") (part "R-US_R0805"))
    )
    (comp (ref "R12")
      (value "100K")
      (footprint "eagle-import:R0805")
      (libsource (lib "eagle-import") (part "R-US_R0805"))
    )
    (comp (ref "R13")
      (value "510")
      (footprint "eagle-import:R0805")
      (libsource (lib "eagle-import") (part "R-US_R0805"))
    )
    (comp (ref "R14")
      (value "10K")
      (footprint "eagle-import:R0805")
      (libsource (lib "eagle-import") (part "R-US_R0805"))
    )
    (comp (ref "R35")
      (value "510")
      (footprint "eagle-import:R0805")
      (libsource (lib "eagle-import") (part "R-US_R0805"))
    )
    (comp (ref "R36")
      (value "10K")
      (footprint "eagle-import:R0805")
      (libsource (lib "eagle-import") (part "R-US_R0805"))
    )
    (comp (ref "R38")
      (value "220")
      (footprint "eagle-import:R0805")
      (libsource (lib "eagle-import") (part "R-US_R0805"))
    )
    (comp (ref "R45")
      (value "200")
      (footprint "eagle-import:R0805")
      (libsource (lib "eagle-import") (part "R-US_R0805"))
    )
    (comp (ref "R47")
      (value "10K")
      (footprint "eagle-import:R0805")
      (libsource (lib "eagle-import") (part "R-US_R0805"))
    )
    (comp (ref "R48")
      (value "200")
      (footprint "eagle-import:R0805")
      (libsource (lib "eagle-import") (part "R-US_R0805"))
    )
    (comp (ref "R49")
      (value "10K")
      (footprint "eagle-import:R0805")
      (libsource (lib "eagle-import") (part "R-US_R0805"))
    )
    (comp (ref "R50")
      (value "100K")
      (footprint "eagle-import:R0805")
      (libsource (lib "eagle-import") (part "R-US_R0805"))
    )
    (comp (ref "R51")
      (value "510")
      (footprint "eagle-import:R0805")
      (libsource (lib "eagle-import") (part "R-US_R0805"))
    )
    (comp (ref "R52")
      (value "100K")
      (footprint "eagle-import:R0805")
      (libsource (lib "eagle-import") (part "R-US_R0805"))
    )
    (comp (ref "R56")
      (value "200")
      (footprint "eagle-import:R0805")
      (libsource (lib "eagle-import") (part "R-US_R0805"))
    )
    (comp (ref "RST")
      (value "RED")
      (footprint "eagle-import:CHIPLED_0805")
      (libsource (lib "eagle-import") (part "LEDCHIPLED_0805"))
    )
    (comp (ref "C11")
      (value "10uF")
      (footprint "eagle-import:C1206")
      (libsource (lib "eagle-import") (part "resistor_348_C-EUC1206"))
    )
    (comp (ref "C12")
      (value "10uF")
      (footprint "eagle-import:C1206")
      (libsource (lib "eagle-import") (part "resistor_348_C-EUC1206"))
    )
    (comp (ref "C21")
      (value "10pF")
      (footprint "eagle-import:C1206")
      (libsource (lib "eagle-import") (part "resistor_348_C-EUC1206"))
    )
    (comp (ref "C22")
      (value "10pF")
      (footprint "eagle-import:C1206")
      (libsource (lib "eagle-import") (part "resistor_348_C-EUC1206"))
    )
    (comp (ref "CMP_BRKOUT")
      (value "CONN_05X2SHD")
      (footprint "eagle-import:2X5-SHROUDED")
      (libsource (lib "eagle-import") (part "CONN_05X2SHD"))
    )
    (comp (ref "IC3")
      (value "MLX90393ELW-ABA-011-SP")
      (footprint "eagle-import:QFN50P300X300X100-17N")
      (libsource (lib "eagle-import") (part "MLX90393ELW-ABA-011-SP"))
    )
    (comp (ref "R9")
      (value "10K")
      (footprint "eagle-import:R1206")
      (libsource (lib "eagle-import") (part "resistor_348_R-US_R1206"))
    )
    (comp (ref "R10")
      (value "10K")
      (footprint "eagle-import:R1206")
      (libsource (lib "eagle-import") (part "resistor_348_R-US_R1206"))
    )
  )
  (nets
    (net (code "1") (name "CMP_INT") (class "Default")
      (node (ref "COMPASS_HEADER") (pin "4") (pinfunction "4_4") (pintype "passive"))
      (node (ref "IC5") (pin "40") (pinfunction "PE9_40") (pintype "bidirectional"))
    )
    (net (code "2") (name "CMP_MISO") (class "Default")
      (node (ref "IC5") (pin "53") (pinfunction "PB14_53") (pintype "bidirectional"))
      (node (ref "SPI_CMP") (pin "6") (pinfunction "MISO_6") (pintype "bidirectional"))
    )
    (net (code "3") (name "CMP_MOSI") (class "Default")
      (node (ref "IC5") (pin "54") (pinfunction "PB15_54") (pintype "bidirectional"))
      (node (ref "SPI_CMP") (pin "5") (pinfunction "SDA/MOSI_5") (pintype "bidirectional"))
    )
    (net (code "4") (name "CMP_SCL") (class "Default")
      (node (ref "COMPASS_HEADER") (pin "6") (pinfunction "6_6") (pintype "passive"))
      (node (ref "IC5") (pin "95") (pinfunction "PB8_95") (pintype "bidirectional"))
      (node (ref "R47") (pin "1") (pinfunction "1_1") (pintype "passive"))
    )
    (net (code "5") (name "CMP_SCLK") (class "Default")
      (node (ref "IC5") (pin "52") (pinfunction "PB13_52") (pintype "bidirectional"))
      (node (ref "SPI_CMP") (pin "3") (pinfunction "SCL/SCLK_3") (pintype "bidirectional"))
    )
    (net (code "6") (name "CMP_SDA") (class "Default")
      (node (ref "COMPASS_HEADER") (pin "8") (pinfunction "8_8") (pintype "passive"))
      (node (ref "IC5") (pin "96") (pinfunction "PB9_96") (pintype "bidirectional"))
      (node (ref "R49") (pin "1") (pinfunction "1_1") (pintype "passive"))
    )
    (net (code "7") (name "CMP_SPI_INT") (class "Default")
      (node (ref "IC5") (pin "38") (pinfunction "PE7_38") (pintype "bidirectional"))
      (node (ref "SPI_CMP") (pin "1") (pinfunction "INT_1") (pintype "bidirectional"))
    )
    (net (code "8") (name "CMP_TRG") (class "Default")
      (node (ref "COMPASS_HEADER") (pin "10") (pinfunction "10_10") (pintype "passive"))
      (node (ref "IC5") (pin "41") (pinfunction "PE10_41") (pintype "bidirectional"))
    )
    (net (code "9") (name "CMP_TRIG") (class "Default")
      (node (ref "IC5") (pin "39") (pinfunction "PE8_39") (pintype "bidirectional"))
      (node (ref "SPI_CMP") (pin "7") (pinfunction "INT/TRIG_7") (pintype "bidirectional"))
    )
    (net (code "10") (name "C_MOS") (class "Default")
      (node (ref "CON_SW") (pin "G") (pinfunction "G_G") (pintype "passive"))
      (node (ref "IC5") (pin "69") (pinfunction "PA10_69") (pintype "bidirectional"))
      (node (ref "R15") (pin "2") (pinfunction "2_2") (pintype "passive"))
    )
    (net (code "11") (name "ESP_GPIO0") (class "Default")
      (node (ref "ESP8266_HEADER") (pin "5") (pinfunction "5_5") (pintype "passive"))
      (node (ref "ESP_DEBUG") (pin "8") (pinfunction "8_8") (pintype "passive"))
      (node (ref "JP2") (pin "3") (pinfunction "3_3") (pintype "passive"))
    )
    (net (code "12") (name "ESP_GPIO2") (class "Default")
      (node (ref "BOOT0") (pin "G") (pinfunction "G_G") (pintype "passive"))
      (node (ref "ESP8266_HEADER") (pin "3") (pinfunction "3_3") (pintype "passive"))
      (node (ref "ESP_DEBUG") (pin "7") (pinfunction "7_7") (pintype "passive"))
      (node (ref "R50") (pin "2") (pinfunction "2_2") (pintype "passive"))
    )
    (net (code "13") (name "ESP_RX") (class "Default")
      (node (ref "ESP8266_HEADER") (pin "7") (pinfunction "7_7") (pintype "passive"))
      (node (ref "ESP_DEBUG") (pin "4") (pinfunction "4_4") (pintype "passive"))
      (node (ref "IC5") (pin "47") (pinfunction "PB10_47") (pintype "bidirectional"))
    )
    (net (code "14") (name "ESP_TX") (class "Default")
      (node (ref "ESP8266_HEADER") (pin "2") (pinfunction "2_2") (pintype "passive"))
      (node (ref "ESP_DEBUG") (pin "5") (pinfunction "5_5") (pintype "passive"))
      (node (ref "IC5") (pin "48") (pinfunction "PB11_48") (pintype "bidirectional"))
    )
    (net (code "15") (name "GND") (class "Default")
      (node (ref "C1") (pin "-") (pinfunction "-_-") (pintype "passive"))
      (node (ref "C10") (pin "2") (pinfunction "2_2") (pintype "passive"))
      (node (ref "C13") (pin "1") (pinfunction "1_1") (pintype "passive"))
      (node (ref "C14") (pin "2") (pinfunction "2_2") (pintype "passive"))
      (node (ref "C18") (pin "2") (pinfunction "2_2") (pintype "passive"))
      (node (ref "C2") (pin "-") (pinfunction "-_-") (pintype "passive"))
      (node (ref "C25") (pin "2") (pinfunction "2_2") (pintype "passive"))
      (node (ref "C26") (pin "2") (pinfunction "2_2") (pintype "passive"))
      (node (ref "C3") (pin "-") (pinfunction "-_-") (pintype "passive"))
      (node (ref "C30") (pin "2") (pinfunction "2_2") (pintype "passive"))
      (node (ref "C31") (pin "2") (pinfunction "2_2") (pintype "passive"))
      (node (ref "C32") (pin "1") (pinfunction "1_1") (pintype "passive"))
      (node (ref "C33") (pin "1") (pinfunction "1_1") (pintype "passive"))
      (node (ref "C34") (pin "2") (pinfunction "2_2") (pintype "passive"))
      (node (ref "C35") (pin "2") (pinfunction "2_2") (pintype "passive"))
      (node (ref "C38") (pin "1") (pinfunction "1_1") (pintype "passive"))
      (node (ref "C39") (pin "2") (pinfunction "2_2") (pintype "passive"))
      (node (ref "C4") (pin "-") (pinfunction "-_-") (pintype "passive"))
      (node (ref "C40") (pin "2") (pinfunction "2_2") (pintype "passive"))
      (node (ref "C41") (pin "2") (pinfunction "2_2") (pintype "passive"))
      (node (ref "C42") (pin "2") (pinfunction "2_2") (pintype "passive"))
      (node (ref "C43") (pin "2") (pinfunction "2_2") (pintype "passive"))
      (node (ref "C44") (pin "2") (pinfunction "2_2") (pintype "passive"))
      (node (ref "C45") (pin "2") (pinfunction "2_2") (pintype "passive"))
      (node (ref "C5") (pin "2") (pinfunction "2_2") (pintype "passive"))
      (node (ref "COMPASS_HEADER") (pin "3") (pinfunction "3_3") (pintype "passive"))
      (node (ref "COMPASS_HEADER") (pin "5") (pinfunction "5_5") (pintype "passive"))
      (node (ref "COMPASS_HEADER") (pin "7") (pinfunction "7_7") (pintype "passive"))
      (node (ref "COMPASS_HEADER") (pin "9") (pinfunction "9_9") (pintype "passive"))
      (node (ref "CONVPOW") (pin "1") (pinfunction "GND_1") (pintype "power_in"))
      (node (ref "CON_SW") (pin "S") (pinfunction "S_S") (pintype "passive"))
      (node (ref "DCIN") (pin "1") (pinfunction "GND_1") (pintype "power_in"))
      (node (ref "DCOUT") (pin "1") (pinfunction "GND_1") (pintype "power_in"))
      (node (ref "ESP8266_HEADER") (pin "1") (pinfunction "1_1") (pintype "passive"))
      (node (ref "ESP_DEBUG") (pin "1") (pinfunction "1_1") (pintype "passive"))
      (node (ref "GPS_DEBUG") (pin "1") (pinfunction "1_1") (pintype "passive"))
      (node (ref "GPS_HEADER") (pin "4") (pinfunction "4_4") (pintype "passive"))
      (node (ref "IC5") (pin "10") (pinfunction "VSS_10") (pintype "passive"))
      (node (ref "IC5") (pin "20") (pinfunction "VSSA_20") (pintype "passive"))
      (node (ref "IC5") (pin "27") (pinfunction "VSS_27") (pintype "passive"))
      (node (ref "IC5") (pin "74") (pinfunction "VSS_74") (pintype "passive"))
      (node (ref "IC5") (pin "99") (pinfunction "VSS_99") (pintype "passive"))
      (node (ref "LASR_SW") (pin "S") (pinfunction "S_S") (pintype "passive"))
      (node (ref "LDR_SW") (pin "S") (pinfunction "S_S") (pintype "passive"))
      (node (ref "LED1") (pin "C") (pinfunction "C_C") (pintype "passive"))
      (node (ref "LEFT_MOTOR") (pin "3") (pinfunction "3_3") (pintype "bidirectional"))
      (node (ref "LEFT_MOTOR") (pin "5") (pinfunction "5_5") (pintype "bidirectional"))
      (node (ref "LM_SW") (pin "S") (pinfunction "S_S") (pintype "passive"))
      (node (ref "LTE_PWR") (pin "4") (pinfunction "4_4") (pintype "bidirectional"))
      (node (ref "LTE_SW_REG") (pin "2") (pinfunction "COMMON(GROUND)_2") (pintype "bidirectional"))
      (node (ref "MICRO_REG") (pin "1") (pinfunction "ADJ/GND_1") (pintype "power_in"))
      (node (ref "MICRO_SW_REG") (pin "2") (pinfunction "COMMON(GROUND)_2") (pintype "bidirectional"))
      (node (ref "MOTOR_L_SENSE_IN") (pin "P$4") (pinfunction "1_P$4") (pintype "passive"))
      (node (ref "MOTOR_L_SENSE_OUT") (pin "P$4") (pinfunction "1_P$4") (pintype "passive"))
      (node (ref "MOTOR_R_SENSE_IN") (pin "P$4") (pinfunction "1_P$4") (pintype "passive"))
      (node (ref "MOTOR_R_SENSE_OUT") (pin "P$4") (pinfunction "1_P$4") (pintype "passive"))
      (node (ref "NRST") (pin "S") (pinfunction "S_S") (pintype "passive"))
      (node (ref "PCBPOWER") (pin "1") (pinfunction "GND_1") (pintype "power_in"))
      (node (ref "PCB_SENSE_IN") (pin "P$4") (pinfunction "1_P$4") (pintype "passive"))
      (node (ref "PCB_SENSE_OUT") (pin "P$4") (pinfunction "1_P$4") (pintype "passive"))
      (node (ref "PWR") (pin "C") (pinfunction "C_C") (pintype "passive"))
      (node (ref "R13") (pin "1") (pinfunction "1_1") (pintype "passive"))
      (node (ref "R15") (pin "1") (pinfunction "1_1") (pintype "passive"))
      (node (ref "R18") (pin "2") (pinfunction "2_2") (pintype "passive"))
      (node (ref "R2") (pin "2") (pinfunction "2_2") (pintype "passive"))
      (node (ref "R20") (pin "2") (pinfunction "2_2") (pintype "passive"))
      (node (ref "R22") (pin "2") (pinfunction "2_2") (pintype "passive"))
      (node (ref "R24") (pin "2") (pinfunction "2_2") (pintype "passive"))
      (node (ref "R26") (pin "2") (pinfunction "2_2") (pintype "passive"))
      (node (ref "R28") (pin "2") (pinfunction "2_2") (pintype "passive"))
      (node (ref "R30") (pin "2") (pinfunction "2_2") (pintype "passive"))
      (node (ref "R32") (pin "2") (pinfunction "2_2") (pintype "passive"))
      (node (ref "R34") (pin "2") (pinfunction "2_2") (pintype "passive"))
      (node (ref "R35") (pin "1") (pinfunction "1_1") (pintype "passive"))
      (node (ref "R4") (pin "2") (pinfunction "2_2") (pintype "passive"))
      (node (ref "R46") (pin "1") (pinfunction "1_1") (pintype "passive"))
      (node (ref "R50") (pin "1") (pinfunction "1_1") (pintype "passive"))
      (node (ref "R51") (pin "2") (pinfunction "2_2") (pintype "passive"))
      (node (ref "R53") (pin "1") (pinfunction "1_1") (pintype "passive"))
      (node (ref "R6") (pin "2") (pinfunction "2_2") (pintype "passive"))
      (node (ref "R8") (pin "2") (pinfunction "2_2") (pintype "passive"))
      (node (ref "RASPI_PWR") (pin "4") (pinfunction "4_4") (pintype "bidirectional"))
      (node (ref "RASPI_SW") (pin "S") (pinfunction "S_S") (pintype "passive"))
      (node (ref "RIGHT_MOTOR") (pin "3") (pinfunction "3_3") (pintype "bidirectional"))
      (node (ref "RIGHT_MOTOR") (pin "5") (pinfunction "5_5") (pintype "bidirectional"))
      (node (ref "RM_SW") (pin "S") (pinfunction "S_S") (pintype "passive"))
      (node (ref "SOLAR") (pin "1") (pinfunction "GND_1") (pintype "power_in"))
      (node (ref "SPI_CMP") (pin "10") (pinfunction "N/C_3_10") (pintype "bidirectional"))
      (node (ref "SPI_CMP") (pin "11") (pinfunction "A1_11") (pintype "bidirectional"))
      (node (ref "SPI_CMP") (pin "12") (pinfunction "A0_12") (pintype "bidirectional"))
      (node (ref "SPI_CMP") (pin "13") (pinfunction "VSS_13") (pintype "bidirectional"))
      (node (ref "SPI_CMP") (pin "14") (pinfunction "N/C_4_14") (pintype "bidirectional"))
      (node (ref "SPI_CMP") (pin "16") (pinfunction "N/C_5_16") (pintype "bidirectional"))
      (node (ref "SPI_CMP") (pin "2") (pinfunction "SENB/CS_2") (pintype "bidirectional"))
      (node (ref "SPI_CMP") (pin "4") (pinfunction "N/C_1_4") (pintype "bidirectional"))
      (node (ref "SPI_CMP") (pin "9") (pinfunction "N/C_2_9") (pintype "bidirectional"))
      (node (ref "STLINK") (pin "3") (pinfunction "3_3") (pintype "passive"))
    )
    (net (code "16") (name "GPS_RX") (class "Default")
      (node (ref "GPS_DEBUG") (pin "4") (pinfunction "4_4") (pintype "passive"))
      (node (ref "GPS_HEADER") (pin "2") (pinfunction "2_2") (pintype "passive"))
      (node (ref "IC5") (pin "92") (pinfunction "PB6_92") (pintype "bidirectional"))
    )
    (net (code "17") (name "GPS_TX") (class "Default")
      (node (ref "GPS_DEBUG") (pin "5") (pinfunction "5_5") (pintype "passive"))
      (node (ref "GPS_HEADER") (pin "3") (pinfunction "3_3") (pintype "passive"))
      (node (ref "IC5") (pin "93") (pinfunction "PB7_93") (pintype "bidirectional"))
    )
    (net (code "18") (name "LASER_MOS") (class "Default")
      (node (ref "IC5") (pin "71") (pinfunction "PA12_71") (pintype "bidirectional"))
      (node (ref "LASR_SW") (pin "G") (pinfunction "G_G") (pintype "passive"))
      (node (ref "R55") (pin "1") (pinfunction "1_1") (pintype "passive"))
    )
    (net (code "19") (name "LDR0") (class "Default")
      (node (ref "IC5") (pin "23") (pinfunction "PA0_23") (pintype "bidirectional"))
      (node (ref "LDR0") (pin "TP") (pinfunction "TP_TP") (pintype "input"))
      (node (ref "LDR_HEADER") (pin "2") (pinfunction "2_2") (pintype "passive"))
      (node (ref "R37") (pin "1") (pinfunction "1_1") (pintype "passive"))
    )
    (net (code "20") (name "LDR1") (class "Default")
      (node (ref "IC5") (pin "24") (pinfunction "PA1_24") (pintype "bidirectional"))
      (node (ref "LDR1") (pin "TP") (pinfunction "TP_TP") (pintype "input"))
      (node (ref "LDR_HEADER") (pin "4") (pinfunction "4_4") (pintype "passive"))
      (node (ref "R39") (pin "1") (pinfunction "1_1") (pintype "passive"))
    )
    (net (code "21") (name "LDR2") (class "Default")
      (node (ref "IC5") (pin "25") (pinfunction "PA2_25") (pintype "bidirectional"))
      (node (ref "LDR2") (pin "TP") (pinfunction "TP_TP") (pintype "input"))
      (node (ref "LDR_HEADER") (pin "6") (pinfunction "6_6") (pintype "passive"))
      (node (ref "R40") (pin "1") (pinfunction "1_1") (pintype "passive"))
    )
    (net (code "22") (name "LDR3") (class "Default")
      (node (ref "IC5") (pin "26") (pinfunction "PA3_26") (pintype "bidirectional"))
      (node (ref "LDR3") (pin "TP") (pinfunction "TP_TP") (pintype "input"))
      (node (ref "LDR_HEADER") (pin "8") (pinfunction "8_8") (pintype "passive"))
      (node (ref "R41") (pin "1") (pinfunction "1_1") (pintype "passive"))
    )
    (net (code "23") (name "LDR4") (class "Default")
      (node (ref "IC5") (pin "29") (pinfunction "PA4_29") (pintype "bidirectional"))
      (node (ref "LDR4") (pin "TP") (pinfunction "TP_TP") (pintype "input"))
      (node (ref "LDR_HEADER") (pin "10") (pinfunction "10_10") (pintype "passive"))
      (node (ref "R42") (pin "1") (pinfunction "1_1") (pintype "passive"))
    )
    (net (code "24") (name "LDR_MOS") (class "Default")
      (node (ref "IC5") (pin "77") (pinfunction "PA15_77") (pintype "bidirectional"))
      (node (ref "LDR_SW") (pin "G") (pinfunction "G_G") (pintype "passive"))
      (node (ref "R54") (pin "1") (pinfunction "1_1") (pintype "passive"))
    )
    (net (code "25") (name "L_MOS") (class "Default")
      (node (ref "IC5") (pin "67") (pinfunction "PA8_67") (pintype "bidirectional"))
      (node (ref "LM_SW") (pin "G") (pinfunction "G_G") (pintype "passive"))
      (node (ref "R46") (pin "2") (pinfunction "2_2") (pintype "passive"))
    )
    (net (code "26") (name "L_PWM") (class "Default")
      (node (ref "IC5") (pin "63") (pinfunction "PC6_63") (pintype "bidirectional"))
      (node (ref "LEFT_MOTOR") (pin "1") (pinfunction "1_1") (pintype "bidirectional"))
    )
    (net (code "27") (name "MOTOR_L_CELL1") (class "Default")
      (node (ref "IC5") (pin "35") (pinfunction "PB0_35") (pintype "bidirectional"))
      (node (ref "L_CELL1") (pin "TP") (pinfunction "TP_TP") (pintype "input"))
      (node (ref "R27") (pin "2") (pinfunction "2_2") (pintype "passive"))
      (node (ref "R28") (pin "1") (pinfunction "1_1") (pintype "passive"))
    )
    (net (code "28") (name "MOTOR_L_CELL2") (class "Default")
      (node (ref "IC5") (pin "36") (pinfunction "PB1_36") (pintype "bidirectional"))
      (node (ref "L_CELL2") (pin "TP") (pinfunction "TP_TP") (pintype "input"))
      (node (ref "R25") (pin "2") (pinfunction "2_2") (pintype "passive"))
      (node (ref "R26") (pin "1") (pinfunction "1_1") (pintype "passive"))
    )
    (net (code "29") (name "MOTOR_L_CELL3") (class "Default")
      (node (ref "IC5") (pin "15") (pinfunction "PC0_15") (pintype "bidirectional"))
      (node (ref "L_CELL3") (pin "TP") (pinfunction "TP_TP") (pintype "input"))
      (node (ref "R23") (pin "2") (pinfunction "2_2") (pintype "passive"))
      (node (ref "R24") (pin "1") (pinfunction "1_1") (pintype "passive"))
    )
    (net (code "30") (name "MOTOR_R_CELL1") (class "Default")
      (node (ref "IC5") (pin "16") (pinfunction "PC1_16") (pintype "bidirectional"))
      (node (ref "R33") (pin "2") (pinfunction "2_2") (pintype "passive"))
      (node (ref "R34") (pin "1") (pinfunction "1_1") (pintype "passive"))
      (node (ref "R_CELL1") (pin "TP") (pinfunction "TP_TP") (pintype "input"))
    )
    (net (code "31") (name "MOTOR_R_CELL2") (class "Default")
      (node (ref "IC5") (pin "17") (pinfunction "PC2_17") (pintype "bidirectional"))
      (node (ref "R31") (pin "2") (pinfunction "2_2") (pintype "passive"))
      (node (ref "R32") (pin "1") (pinfunction "1_1") (pintype "passive"))
      (node (ref "R_CELL2") (pin "TP") (pinfunction "TP_TP") (pintype "input"))
    )
    (net (code "32") (name "MOTOR_R_CELL3") (class "Default")
      (node (ref "IC5") (pin "18") (pinfunction "PC3_18") (pintype "bidirectional"))
      (node (ref "R29") (pin "2") (pinfunction "2_2") (pintype "passive"))
      (node (ref "R30") (pin "1") (pinfunction "1_1") (pintype "passive"))
      (node (ref "R_CELL3") (pin "TP") (pinfunction "TP_TP") (pintype "input"))
    )
    (net (code "33") (name "NRST") (class "Default")
      (node (ref "NRST") (pin "D") (pinfunction "D_D") (pintype "passive"))
      (node (ref "RST") (pin "C") (pinfunction "C_C") (pintype "passive"))
      (node (ref "STLINK") (pin "5") (pinfunction "5_5") (pintype "passive"))
    )
    (net (code "34") (name "Net-(BOOT0-PadD)") (class "Default")
      (node (ref "BOOT0") (pin "D") (pinfunction "D_D") (pintype "passive"))
      (node (ref "JP1") (pin "3") (pinfunction "3_3") (pintype "passive"))
      (node (ref "R36") (pin "1") (pinfunction "1_1") (pintype "passive"))
    )
    (net (code "35") (name "Net-(BOOT0-PadS)") (class "Default")
      (node (ref "BOOT0") (pin "S") (pinfunction "S_S") (pintype "passive"))
      (node (ref "R51") (pin "1") (pinfunction "1_1") (pintype "passive"))
    )
    (net (code "36") (name "Net-(C39-Pad1)") (class "Default")
      (node (ref "C39") (pin "1") (pinfunction "1_1") (pintype "passive"))
      (node (ref "Q11") (pin "2") (pinfunction "2_2") (pintype "passive"))
      (node (ref "R38") (pin "2") (pinfunction "2_2") (pintype "passive"))
    )
    (net (code "37") (name "Net-(CONVPOW-POS)") (class "Default")
      (node (ref "CONVPOW") (pin "2") (pinfunction "POS_2") (pintype "power_in"))
      (node (ref "CONV_SW_REG") (pin "3") (pinfunction "POSITIVE_OUTPUT_3") (pintype "bidirectional"))
    )
    (net (code "38") (name "Net-(CONV_SW_REG-COMMON(GROUND))") (class "Default")
      (node (ref "CONV_SW_REG") (pin "2") (pinfunction "COMMON(GROUND)_2") (pintype "bidirectional"))
      (node (ref "CON_SW") (pin "D") (pinfunction "D_D") (pintype "passive"))
      (node (ref "R43") (pin "2") (pinfunction "2_2") (pintype "passive"))
    )
    (net (code "39") (name "Net-(D1-ANODE_1)") (class "Default")
      (node (ref "D1") (pin "1") (pinfunction "ANODE_1_1") (pintype "bidirectional"))
      (node (ref "D1") (pin "2") (pinfunction "ANODE_2_2") (pintype "bidirectional"))
      (node (ref "DCIN") (pin "2") (pinfunction "POS_2") (pintype "power_in"))
    )
    (net (code "40") (name "Net-(D1-CATHODE_(HEATSINK))") (class "Default")
      (node (ref "D1") (pin "3") (pinfunction "CATHODE_(HEATSINK)_3") (pintype "bidirectional"))
      (node (ref "D3") (pin "3") (pinfunction "CATHODE_(HEATSINK)_3") (pintype "bidirectional"))
      (node (ref "DCOUT") (pin "2") (pinfunction "POS_2") (pintype "power_in"))
    )
    (net (code "41") (name "Net-(D3-ANODE_1)") (class "Default")
      (node (ref "D3") (pin "1") (pinfunction "ANODE_1_1") (pintype "bidirectional"))
      (node (ref "D3") (pin "2") (pinfunction "ANODE_2_2") (pintype "bidirectional"))
      (node (ref "SOLAR") (pin "2") (pinfunction "POS_2") (pintype "power_in"))
    )
    (net (code "42") (name "Net-(ESP8266_HEADER-Pad4)") (class "Default")
      (node (ref "ESP8266_HEADER") (pin "4") (pinfunction "4_4") (pintype "passive"))
      (node (ref "ESP8266_HEADER") (pin "8") (pinfunction "8_8") (pintype "passive"))
      (node (ref "JP4") (pin "2") (pinfunction "2_2") (pintype "passive"))
    )
    (net (code "43") (name "Net-(ESP_DEBUG-Pad3)") (class "Default")
      (node (ref "ESP_DEBUG") (pin "3") (pinfunction "3_3") (pintype "passive"))
      (node (ref "JP4") (pin "3") (pinfunction "3_3") (pintype "passive"))
    )
    (net (code "44") (name "Net-(GPS_DEBUG-Pad3)") (class "Default")
      (node (ref "GPS_DEBUG") (pin "3") (pinfunction "3_3") (pintype "passive"))
      (node (ref "JP5") (pin "1") (pinfunction "1_1") (pintype "passive"))
    )
    (net (code "45") (name "Net-(GPS_HEADER-Pad1)") (class "Default")
      (node (ref "GPS_HEADER") (pin "1") (pinfunction "1_1") (pintype "passive"))
      (node (ref "JP5") (pin "3") (pinfunction "3_3") (pintype "passive"))
    )
    (net (code "46") (name "Net-(IC3-A0)") (class "Default")
      (node (ref "C11") (pin "1") (pinfunction "1_1") (pintype "passive"))
      (node (ref "C12") (pin "1") (pinfunction "1_1") (pintype "passive"))
      (node (ref "CMP_BRKOUT") (pin "1") (pinfunction "1_1") (pintype "passive"))
      (node (ref "CMP_BRKOUT") (pin "2") (pinfunction "2_2") (pintype "passive"))
      (node (ref "IC3") (pin "11") (pinfunction "A1_11") (pintype "bidirectional"))
      (node (ref "IC3") (pin "12") (pinfunction "A0_12") (pintype "bidirectional"))
      (node (ref "IC3") (pin "15") (pinfunction "VDD_15") (pintype "bidirectional"))
      (node (ref "IC3") (pin "2") (pinfunction "SENB/CS_2") (pintype "bidirectional"))
      (node (ref "IC3") (pin "8") (pinfunction "VDD_IO_8") (pintype "bidirectional"))
      (node (ref "R10") (pin "1") (pinfunction "1_1") (pintype "passive"))
      (node (ref "R9") (pin "1") (pinfunction "1_1") (pintype "passive"))
    )
    (net (code "47") (name "Net-(IC3-INT)") (class "Default")
      (node (ref "CMP_BRKOUT") (pin "4") (pinfunction "4_4") (pintype "passive"))
      (node (ref "IC3") (pin "1") (pinfunction "INT_1") (pintype "bidirectional"))
    )
    (net (code "48") (name "Net-(IC3-INT{slash}TRIG)") (class "Default")
      (node (ref "CMP_BRKOUT") (pin "10") (pinfunction "10_10") (pintype "passive"))
      (node (ref "IC3") (pin "7") (pinfunction "INT/TRIG_7") (pintype "bidirectional"))
    )
    (net (code "49") (name "Net-(IC3-N{slash}C_1)") (class "Default")
      (node (ref "C11") (pin "2") (pinfunction "2_2") (pintype "passive"))
      (node (ref "C12") (pin "2") (pinfunction "2_2") (pintype "passive"))
      (node (ref "C21") (pin "1") (pinfunction "1_1") (pintype "passive"))
      (node (ref "C22") (pin "1") (pinfunction "1_1") (pintype "passive"))
      (node (ref "CMP_BRKOUT") (pin "3") (pinfunction "3_3") (pintype "passive"))
      (node (ref "CMP_BRKOUT") (pin "5") (pinfunction "5_5") (pintype "passive"))
      (node (ref "CMP_BRKOUT") (pin "7") (pinfunction "7_7") (pintype "passive"))
      (node (ref "CMP_BRKOUT") (pin "9") (pinfunction "9_9") (pintype "passive"))
      (node (ref "IC3") (pin "10") (pinfunction "N/C_3_10") (pintype "bidirectional"))
      (node (ref "IC3") (pin "13") (pinfunction "VSS_13") (pintype "bidirectional"))
      (node (ref "IC3") (pin "14") (pinfunction "N/C_4_14") (pintype "bidirectional"))
      (node (ref "IC3") (pin "16") (pinfunction "N/C_5_16") (pintype "bidirectional"))
      (node (ref "IC3") (pin "4") (pinfunction "N/C_1_4") (pintype "bidirectional"))
      (node (ref "IC3") (pin "9") (pinfunction "N/C_2_9") (pintype "bidirectional"))
    )
    (net (code "50") (name "Net-(IC3-SCL{slash}SCLK)") (class "Default")
      (node (ref "C22") (pin "2") (pinfunction "2_2") (pintype "passive"))
      (node (ref "CMP_BRKOUT") (pin "6") (pinfunction "6_6") (pintype "passive"))
      (node (ref "IC3") (pin "3") (pinfunction "SCL/SCLK_3") (pintype "bidirectional"))
      (node (ref "R10") (pin "2") (pinfunction "2_2") (pintype "passive"))
    )
    (net (code "51") (name "Net-(IC3-SDA{slash}MOSI)") (class "Default")
      (node (ref "C21") (pin "2") (pinfunction "2_2") (pintype "passive"))
      (node (ref "CMP_BRKOUT") (pin "8") (pinfunction "8_8") (pintype "passive"))
      (node (ref "IC3") (pin "5") (pinfunction "SDA/MOSI_5") (pintype "bidirectional"))
      (node (ref "R9") (pin "2") (pinfunction "2_2") (pintype "passive"))
    )
    (net (code "52") (name "Net-(IC5-BOOT0)") (class "Default")
      (node (ref "IC5") (pin "94") (pinfunction "BOOT0_94") (pintype "input"))
      (node (ref "JP1") (pin "2") (pinfunction "2_2") (pintype "passive"))
    )
    (net (code "53") (name "Net-(IC5-NRST)") (class "Default")
      (node (ref "C5") (pin "1") (pinfunction "1_1") (pintype "passive"))
      (node (ref "IC5") (pin "14") (pinfunction "NRST_14") (pintype "bidirectional"))
      (node (ref "R12") (pin "2") (pinfunction "2_2") (pintype "passive"))
      (node (ref "R56") (pin "2") (pinfunction "2_2") (pintype "passive"))
    )
    (net (code "54") (name "Net-(IC5-PB2)") (class "Default")
      (node (ref "IC5") (pin "37") (pinfunction "PB2_37") (pintype "bidirectional"))
      (node (ref "JP3") (pin "2") (pinfunction "2_2") (pintype "passive"))
    )
    (net (code "55") (name "Net-(IC5-PD15)") (class "Default")
      (node (ref "IC5") (pin "62") (pinfunction "PD15_62") (pintype "bidirectional"))
      (node (ref "R45") (pin "1") (pinfunction "1_1") (pintype "passive"))
    )
    (net (code "56") (name "Net-(IC5-PH0)") (class "Default")
      (node (ref "C40") (pin "1") (pinfunction "1_1") (pintype "passive"))
      (node (ref "IC5") (pin "12") (pinfunction "PH0_12") (pintype "bidirectional"))
      (node (ref "Q11") (pin "1") (pinfunction "1_1") (pintype "passive"))
    )
    (net (code "57") (name "Net-(IC5-PH1)") (class "Default")
      (node (ref "IC5") (pin "13") (pinfunction "PH1_13") (pintype "bidirectional"))
      (node (ref "R38") (pin "1") (pinfunction "1_1") (pintype "passive"))
    )
    (net (code "58") (name "Net-(IC5-VCAP_1)") (class "Default")
      (node (ref "C33") (pin "2") (pinfunction "2_2") (pintype "passive"))
      (node (ref "IC5") (pin "49") (pinfunction "VCAP_1_49") (pintype "power_in"))
    )
    (net (code "59") (name "Net-(IC5-VCAP_2)") (class "Default")
      (node (ref "C32") (pin "2") (pinfunction "2_2") (pintype "passive"))
      (node (ref "IC5") (pin "73") (pinfunction "VCAP_2_73") (pintype "power_in"))
    )
    (net (code "60") (name "Net-(IC5-VDDA)") (class "Default")
      (node (ref "C31") (pin "1") (pinfunction "1_1") (pintype "passive"))
      (node (ref "C34") (pin "1") (pinfunction "1_1") (pintype "passive"))
      (node (ref "IC5") (pin "22") (pinfunction "VDDA_22") (pintype "power_in"))
      (node (ref "L1") (pin "1") (pinfunction "1_1") (pintype "passive"))
      (node (ref "R11") (pin "2") (pinfunction "2_2") (pintype "passive"))
    )
    (net (code "61") (name "Net-(IC5-VREF+)") (class "Default")
      (node (ref "C30") (pin "1") (pinfunction "1_1") (pintype "passive"))
      (node (ref "C35") (pin "1") (pinfunction "1_1") (pintype "passive"))
      (node (ref "IC5") (pin "21") (pinfunction "VREF+_21") (pintype "power_in"))
      (node (ref "R11") (pin "1") (pinfunction "1_1") (pintype "passive"))
    )
    (net (code "62") (name "Net-(JP1-Pad1)") (class "Default")
      (node (ref "JP1") (pin "1") (pinfunction "1_1") (pintype "passive"))
      (node (ref "R35") (pin "2") (pinfunction "2_2") (pintype "passive"))
    )
    (net (code "63") (name "Net-(JP2-Pad2)") (class "Default")
      (node (ref "JP2") (pin "2") (pinfunction "2_2") (pintype "passive"))
      (node (ref "NRST") (pin "G") (pinfunction "G_G") (pintype "passive"))
      (node (ref "R52") (pin "2") (pinfunction "2_2") (pintype "passive"))
    )
    (net (code "64") (name "Net-(JP3-Pad1)") (class "Default")
      (node (ref "JP3") (pin "1") (pinfunction "1_1") (pintype "passive"))
      (node (ref "R14") (pin "2") (pinfunction "2_2") (pintype "passive"))
    )
    (net (code "65") (name "Net-(JP3-Pad3)") (class "Default")
      (node (ref "JP3") (pin "3") (pinfunction "3_3") (pintype "passive"))
      (node (ref "R13") (pin "2") (pinfunction "2_2") (pintype "passive"))
    )
    (net (code "66") (name "Net-(LASER_HEADER-Pad1)") (class "Default")
      (node (ref "LASER_HEADER") (pin "1") (pinfunction "1_1") (pintype "passive"))
      (node (ref "LASER_HEADER") (pin "3") (pinfunction "3_3") (pintype "passive"))
      (node (ref "LASER_HEADER") (pin "5") (pinfunction "5_5") (pintype "passive"))
      (node (ref "LASER_HEADER") (pin "7") (pinfunction "7_7") (pintype "passive"))
      (node (ref "LASER_HEADER") (pin "9") (pinfunction "9_9") (pintype "passive"))
      (node (ref "LASR_SW") (pin "D") (pinfunction "D_D") (pintype "passive"))
    )
    (net (code "67") (name "Net-(LDR_SW-PadD)") (class "Default")
      (node (ref "LDR_SW") (pin "D") (pinfunction "D_D") (pintype "passive"))
      (node (ref "R37") (pin "2") (pinfunction "2_2") (pintype "passive"))
      (node (ref "R39") (pin "2") (pinfunction "2_2") (pintype "passive"))
      (node (ref "R40") (pin "2") (pinfunction "2_2") (pintype "passive"))
      (node (ref "R41") (pin "2") (pinfunction "2_2") (pintype "passive"))
      (node (ref "R42") (pin "2") (pinfunction "2_2") (pintype "passive"))
    )
    (net (code "68") (name "Net-(LED1-PadA)") (class "Default")
      (node (ref "LED1") (pin "A") (pinfunction "A_A") (pintype "passive"))
      (node (ref "R45") (pin "2") (pinfunction "2_2") (pintype "passive"))
    )
    (net (code "69") (name "Net-(LEFT_MOTOR-Pad4)") (class "Default")
      (node (ref "LEFT_MOTOR") (pin "4") (pinfunction "4_4") (pintype "bidirectional"))
      (node (ref "LM_SW") (pin "D") (pinfunction "D_D") (pintype "passive"))
    )
    (net (code "70") (name "Net-(LTE_PWR-Pad2)") (class "Default")
      (node (ref "LTE_PWR") (pin "2") (pinfunction "2_2") (pintype "bidirectional"))
      (node (ref "R7") (pin "2") (pinfunction "2_2") (pintype "passive"))
      (node (ref "R8") (pin "1") (pinfunction "1_1") (pintype "passive"))
    )
    (net (code "71") (name "Net-(LTE_PWR-Pad3)") (class "Default")
      (node (ref "LTE_PWR") (pin "3") (pinfunction "3_3") (pintype "bidirectional"))
      (node (ref "R1") (pin "2") (pinfunction "2_2") (pintype "passive"))
      (node (ref "R2") (pin "1") (pinfunction "1_1") (pintype "passive"))
    )
    (net (code "72") (name "Net-(LTE_SW_REG-POSITIVE_OUTPUT)") (class "Default")
      (node (ref "C1") (pin "+") (pinfunction "+_+") (pintype "passive"))
      (node (ref "LTE_PWR") (pin "1") (pinfunction "1_1") (pintype "bidirectional"))
      (node (ref "LTE_SW_REG") (pin "3") (pinfunction "POSITIVE_OUTPUT_3") (pintype "bidirectional"))
      (node (ref "R1") (pin "1") (pinfunction "1_1") (pintype "passive"))
      (node (ref "R7") (pin "1") (pinfunction "1_1") (pintype "passive"))
    )
    (net (code "73") (name "Net-(MOTOR_L_SENSE_INA-1)") (class "Default")
      (node (ref "MOTOR_L_SENSE_IN") (pin "P$1") (pinfunction "1_P$1") (pintype "passive"))
      (node (ref "MOTOR_L_SENSE_OUT") (pin "P$1") (pinfunction "1_P$1") (pintype "passive"))
      (node (ref "R23") (pin "1") (pinfunction "1_1") (pintype "passive"))
    )
    (net (code "74") (name "Net-(MOTOR_L_SENSE_INB-1)") (class "Default")
      (node (ref "MOTOR_L_SENSE_IN") (pin "P$2") (pinfunction "1_P$2") (pintype "passive"))
      (node (ref "MOTOR_L_SENSE_OUT") (pin "P$2") (pinfunction "1_P$2") (pintype "passive"))
      (node (ref "R25") (pin "1") (pinfunction "1_1") (pintype "passive"))
    )
    (net (code "75") (name "Net-(MOTOR_L_SENSE_INC-1)") (class "Default")
      (node (ref "MOTOR_L_SENSE_IN") (pin "P$3") (pinfunction "1_P$3") (pintype "passive"))
      (node (ref "MOTOR_L_SENSE_OUT") (pin "P$3") (pinfunction "1_P$3") (pintype "passive"))
      (node (ref "R27") (pin "1") (pinfunction "1_1") (pintype "passive"))
    )
    (net (code "76") (name "Net-(MOTOR_R_SENSE_INA-1)") (class "Default")
      (node (ref "MOTOR_R_SENSE_IN") (pin "P$1") (pinfunction "1_P$1") (pintype "passive"))
      (node (ref "MOTOR_R_SENSE_OUT") (pin "P$1") (pinfunction "1_P$1") (pintype "passive"))
      (node (ref "R29") (pin "1") (pinfunction "1_1") (pintype "passive"))
    )
    (net (code "77") (name "Net-(MOTOR_R_SENSE_INB-1)") (class "Default")
      (node (ref "MOTOR_R_SENSE_IN") (pin "P$2") (pinfunction "1_P$2") (pintype "passive"))
      (node (ref "MOTOR_R_SENSE_OUT") (pin "P$2") (pinfunction "1_P$2") (pintype "passive"))
      (node (ref "R31") (pin "1") (pinfunction "1_1") (pintype "passive"))
    )
    (net (code "78") (name "Net-(MOTOR_R_SENSE_INC-1)") (class "Default")
      (node (ref "MOTOR_R_SENSE_IN") (pin "P$3") (pinfunction "1_P$3") (pintype "passive"))
      (node (ref "MOTOR_R_SENSE_OUT") (pin "P$3") (pinfunction "1_P$3") (pintype "passive"))
      (node (ref "R33") (pin "1") (pinfunction "1_1") (pintype "passive"))
    )
    (net (code "79") (name "Net-(PCBPOWER-POS)") (class "Default")
      (node (ref "PCBPOWER") (pin "2") (pinfunction "POS_2") (pintype "power_in"))
      (node (ref "PCB_SW") (pin "1") (pinfunction "GND_1") (pintype "power_in"))
    )
    (net (code "80") (name "Net-(PCB_SENSE_INA-1)") (class "Default")
      (node (ref "PCB_SENSE_IN") (pin "P$1") (pinfunction "1_P$1") (pintype "passive"))
      (node (ref "PCB_SENSE_OUT") (pin "P$1") (pinfunction "1_P$1") (pintype "passive"))
      (node (ref "R17") (pin "1") (pinfunction "1_1") (pintype "passive"))
    )
    (net (code "81") (name "Net-(PCB_SENSE_INB-1)") (class "Default")
      (node (ref "PCB_SENSE_IN") (pin "P$2") (pinfunction "1_P$2") (pintype "passive"))
      (node (ref "PCB_SENSE_OUT") (pin "P$2") (pinfunction "1_P$2") (pintype "passive"))
      (node (ref "R19") (pin "1") (pinfunction "1_1") (pintype "passive"))
    )
    (net (code "82") (name "Net-(PCB_SENSE_INC-1)") (class "Default")
      (node (ref "PCB_SENSE_IN") (pin "P$3") (pinfunction "1_P$3") (pintype "passive"))
      (node (ref "PCB_SENSE_OUT") (pin "P$3") (pinfunction "1_P$3") (pintype "passive"))
      (node (ref "R21") (pin "1") (pinfunction "1_1") (pintype "passive"))
    )
    (net (code "83") (name "Net-(PWR-PadA)") (class "Default")
      (node (ref "PWR") (pin "A") (pinfunction "A_A") (pintype "passive"))
      (node (ref "R48") (pin "2") (pinfunction "2_2") (pintype "passive"))
    )
    (net (code "84") (name "Net-(R3-Pad2)") (class "Default")
      (node (ref "R3") (pin "2") (pinfunction "2_2") (pintype "passive"))
      (node (ref "R4") (pin "1") (pinfunction "1_1") (pintype "passive"))
      (node (ref "RASPI_PWR") (pin "3") (pinfunction "3_3") (pintype "bidirectional"))
    )
    (net (code "85") (name "Net-(R5-Pad2)") (class "Default")
      (node (ref "R5") (pin "2") (pinfunction "2_2") (pintype "passive"))
      (node (ref "R6") (pin "1") (pinfunction "1_1") (pintype "passive"))
      (node (ref "RASPI_PWR") (pin "2") (pinfunction "2_2") (pintype "bidirectional"))
    )
    (net (code "86") (name "Net-(R56-Pad1)") (class "Default")
      (node (ref "R56") (pin "1") (pinfunction "1_1") (pintype "passive"))
      (node (ref "RST") (pin "A") (pinfunction "A_A") (pintype "passive"))
    )
    (net (code "87") (name "Net-(RASPI_SW_REG-COMMON(GROUND))") (class "Default")
      (node (ref "R44") (pin "2") (pinfunction "2_2") (pintype "passive"))
      (node (ref "RASPI_SW") (pin "D") (pinfunction "D_D") (pintype "passive"))
      (node (ref "RASPI_SW_REG") (pin "2") (pinfunction "COMMON(GROUND)_2") (pintype "bidirectional"))
    )
    (net (code "88") (name "Net-(RASPI_SW_REG-POSITIVE_OUTPUT)") (class "Default")
      (node (ref "C2") (pin "+") (pinfunction "+_+") (pintype "passive"))
      (node (ref "R3") (pin "1") (pinfunction "1_1") (pintype "passive"))
      (node (ref "R5") (pin "1") (pinfunction "1_1") (pintype "passive"))
      (node (ref "RASPI_PWR") (pin "1") (pinfunction "1_1") (pintype "bidirectional"))
      (node (ref "RASPI_SW_REG") (pin "3") (pinfunction "POSITIVE_OUTPUT_3") (pintype "bidirectional"))
    )
    (net (code "89") (name "Net-(RIGHT_MOTOR-Pad4)") (class "Default")
      (node (ref "RIGHT_MOTOR") (pin "4") (pinfunction "4_4") (pintype "bidirectional"))
      (node (ref "RM_SW") (pin "D") (pinfunction "D_D") (pintype "passive"))
    )
    (net (code "90") (name "PCB_CELL1") (class "Default")
      (node (ref "IC5") (pin "30") (pinfunction "PA5_30") (pintype "bidirectional"))
      (node (ref "PCB1") (pin "TP") (pinfunction "TP_TP") (pintype "input"))
      (node (ref "R21") (pin "2") (pinfunction "2_2") (pintype "passive"))
      (node (ref "R22") (pin "1") (pinfunction "1_1") (pintype "passive"))
    )
    (net (code "91") (name "PCB_CELL2") (class "Default")
      (node (ref "IC5") (pin "31") (pinfunction "PA6_31") (pintype "bidirectional"))
      (node (ref "PCB2") (pin "TP") (pinfunction "TP_TP") (pintype "input"))
      (node (ref "R19") (pin "2") (pinfunction "2_2") (pintype "passive"))
      (node (ref "R20") (pin "1") (pinfunction "1_1") (pintype "passive"))
    )
    (net (code "92") (name "PCB_CELL3") (class "Default")
      (node (ref "IC5") (pin "32") (pinfunction "PA7_32") (pintype "bidirectional"))
      (node (ref "PCB3") (pin "TP") (pinfunction "TP_TP") (pintype "input"))
      (node (ref "R17") (pin "2") (pinfunction "2_2") (pintype "passive"))
      (node (ref "R18") (pin "1") (pinfunction "1_1") (pintype "passive"))
    )
    (net (code "93") (name "RASPI_MOS") (class "Default")
      (node (ref "IC5") (pin "70") (pinfunction "PA11_70") (pintype "bidirectional"))
      (node (ref "R16") (pin "2") (pinfunction "2_2") (pintype "passive"))
      (node (ref "RASPI_SW") (pin "G") (pinfunction "G_G") (pintype "passive"))
    )
    (net (code "94") (name "R_MOS") (class "Default")
      (node (ref "IC5") (pin "68") (pinfunction "PA9_68") (pintype "bidirectional"))
      (node (ref "R53") (pin "2") (pinfunction "2_2") (pintype "passive"))
      (node (ref "RM_SW") (pin "G") (pinfunction "G_G") (pintype "passive"))
    )
    (net (code "95") (name "R_PWM") (class "Default")
      (node (ref "IC5") (pin "64") (pinfunction "PC7_64") (pintype "bidirectional"))
      (node (ref "RIGHT_MOTOR") (pin "1") (pinfunction "1_1") (pintype "bidirectional"))
    )
    (net (code "96") (name "SWCLK") (class "Default")
      (node (ref "IC5") (pin "76") (pinfunction "PA14_76") (pintype "bidirectional"))
      (node (ref "STLINK") (pin "2") (pinfunction "2_2") (pintype "passive"))
    )
    (net (code "97") (name "SWDIO") (class "Default")
      (node (ref "IC5") (pin "72") (pinfunction "PA13_72") (pintype "bidirectional"))
      (node (ref "STLINK") (pin "4") (pinfunction "4_4") (pintype "passive"))
    )
    (net (code "98") (name "SWO") (class "Default")
      (node (ref "IC5") (pin "89") (pinfunction "PB3_89") (pintype "bidirectional"))
      (node (ref "STLINK") (pin "6") (pinfunction "6_6") (pintype "passive"))
    )
    (net (code "99") (name "VBAT") (class "Default")
      (node (ref "CONV_SW_REG") (pin "1") (pinfunction "POSITIVE_INPUT_1") (pintype "bidirectional"))
      (node (ref "LTE_SW_REG") (pin "1") (pinfunction "POSITIVE_INPUT_1") (pintype "bidirectional"))
      (node (ref "MICRO_SW_REG") (pin "1") (pinfunction "POSITIVE_INPUT_1") (pintype "bidirectional"))
      (node (ref "PCB_SW") (pin "2") (pinfunction "POS_2") (pintype "power_in"))
      (node (ref "R16") (pin "1") (pinfunction "1_1") (pintype "passive"))
      (node (ref "R43") (pin "1") (pinfunction "1_1") (pintype "passive"))
      (node (ref "R44") (pin "1") (pinfunction "1_1") (pintype "passive"))
      (node (ref "RASPI_SW_REG") (pin "1") (pinfunction "POSITIVE_INPUT_1") (pintype "bidirectional"))
    )
    (net (code "100") (name "VCC") (class "Default")
      (node (ref "C13") (pin "2") (pinfunction "2_2") (pintype "passive"))
      (node (ref "C14") (pin "1") (pinfunction "1_1") (pintype "passive"))
      (node (ref "C18") (pin "1") (pinfunction "1_1") (pintype "passive"))
      (node (ref "C25") (pin "1") (pinfunction "1_1") (pintype "passive"))
      (node (ref "C26") (pin "1") (pinfunction "1_1") (pintype "passive"))
      (node (ref "C38") (pin "2") (pinfunction "2_2") (pintype "passive"))
      (node (ref "C4") (pin "+") (pinfunction "+_+") (pintype "passive"))
      (node (ref "C41") (pin "1") (pinfunction "1_1") (pintype "passive"))
      (node (ref "C42") (pin "1") (pinfunction "1_1") (pintype "passive"))
      (node (ref "C43") (pin "1") (pinfunction "1_1") (pintype "passive"))
      (node (ref "C44") (pin "1") (pinfunction "1_1") (pintype "passive"))
      (node (ref "C45") (pin "1") (pinfunction "1_1") (pintype "passive"))
      (node (ref "COMPASS_HEADER") (pin "1") (pinfunction "1_1") (pintype "passive"))
      (node (ref "COMPASS_HEADER") (pin "2") (pinfunction "2_2") (pintype "passive"))
      (node (ref "IC5") (pin "100") (pinfunction "VDD_100") (pintype "power_in"))
      (node (ref "IC5") (pin "11") (pinfunction "VDD_11") (pintype "power_in"))
      (node (ref "IC5") (pin "19") (pinfunction "VDD_19") (pintype "power_in"))
      (node (ref "IC5") (pin "28") (pinfunction "VDD_28") (pintype "power_in"))
      (node (ref "IC5") (pin "50") (pinfunction "VDD_50") (pintype "power_in"))
      (node (ref "IC5") (pin "6") (pinfunction "VBAT_6") (pintype "power_in"))
      (node (ref "IC5") (pin "75") (pinfunction "VDD_75") (pintype "power_in"))
      (node (ref "JP2") (pin "1") (pinfunction "1_1") (pintype "passive"))
      (node (ref "JP4") (pin "1") (pinfunction "1_1") (pintype "passive"))
      (node (ref "JP5") (pin "2") (pinfunction "2_2") (pintype "passive"))
      (node (ref "L1") (pin "2") (pinfunction "2_2") (pintype "passive"))
      (node (ref "MICRO_REG") (pin "2") (pinfunction "VOUT_2") (pintype "output"))
      (node (ref "R12") (pin "1") (pinfunction "1_1") (pintype "passive"))
      (node (ref "R14") (pin "1") (pinfunction "1_1") (pintype "passive"))
      (node (ref "R36") (pin "2") (pinfunction "2_2") (pintype "passive"))
      (node (ref "R47") (pin "2") (pinfunction "2_2") (pintype "passive"))
      (node (ref "R48") (pin "1") (pinfunction "1_1") (pintype "passive"))
      (node (ref "R49") (pin "2") (pinfunction "2_2") (pintype "passive"))
      (node (ref "R52") (pin "1") (pinfunction "1_1") (pintype "passive"))
      (node (ref "R54") (pin "2") (pinfunction "2_2") (pintype "passive"))
      (node (ref "R55") (pin "2") (pinfunction "2_2") (pintype "passive"))
      (node (ref "SPI_CMP") (pin "15") (pinfunction "VDD_15") (pintype "bidirectional"))
      (node (ref "SPI_CMP") (pin "8") (pinfunction "VDD_IO_8") (pintype "bidirectional"))
      (node (ref "STLINK") (pin "1") (pinfunction "1_1") (pintype "passive"))
    )
    (net (code "101") (name "VDD") (class "Default")
      (node (ref "C10") (pin "1") (pinfunction "1_1") (pintype "passive"))
      (node (ref "C3") (pin "+") (pinfunction "+_+") (pintype "passive"))
      (node (ref "LASER_HEADER") (pin "10") (pinfunction "10_10") (pintype "passive"))
      (node (ref "LASER_HEADER") (pin "2") (pinfunction "2_2") (pintype "passive"))
      (node (ref "LASER_HEADER") (pin "4") (pinfunction "4_4") (pintype "passive"))
      (node (ref "LASER_HEADER") (pin "6") (pinfunction "6_6") (pintype "passive"))
      (node (ref "LASER_HEADER") (pin "8") (pinfunction "8_8") (pintype "passive"))
      (node (ref "LDR_HEADER") (pin "1") (pinfunction "1_1") (pintype "passive"))
      (node (ref "LDR_HEADER") (pin "3") (pinfunction "3_3") (pintype "passive"))
      (node (ref "LDR_HEADER") (pin "5") (pinfunction "5_5") (pintype "passive"))
      (node (ref "LDR_HEADER") (pin "7") (pinfunction "7_7") (pintype "passive"))
      (node (ref "LDR_HEADER") (pin "9") (pinfunction "9_9") (pintype "passive"))
      (node (ref "MICRO_REG") (pin "3") (pinfunction "VIN_3") (pintype "input"))
      (node (ref "MICRO_SW_REG") (pin "3") (pinfunction "POSITIVE_OUTPUT_3") (pintype "bidirectional"))
    )
    (net (code "102") (name "unconnected-(ESP8266_HEADER-Pad6)") (class "Default")
      (node (ref "ESP8266_HEADER") (pin "6") (pinfunction "6_6") (pintype "passive"))
    )
    (net (code "103") (name "unconnected-(ESP_DEBUG-Pad2)") (class "Default")
      (node (ref "ESP_DEBUG") (pin "2") (pinfunction "2_2") (pintype "passive"))
    )
    (net (code "104") (name "unconnected-(ESP_DEBUG-Pad6)") (class "Default")
      (node (ref "ESP_DEBUG") (pin "6") (pinfunction "6_6") (pintype "passive"))
    )
    (net (code "105") (name "unconnected-(GPS_DEBUG-Pad2)") (class "Default")
      (node (ref "GPS_DEBUG") (pin "2") (pinfunction "2_2") (pintype "passive"))
    )
    (net (code "106") (name "unconnected-(GPS_DEBUG-Pad6)") (class "Default")
      (node (ref "GPS_DEBUG") (pin "6") (pinfunction "6_6") (pintype "passive"))
    )
    (net (code "107") (name "unconnected-(IC3-MISO-Pad6)") (class "Default")
      (node (ref "IC3") (pin "6") (pinfunction "MISO_6") (pintype "bidirectional"))
    )
    (net (code "108") (name "unconnected-(IC3-THERMAL_PAD-Pad17)") (class "Default")
      (node (ref "IC3") (pin "17") (pinfunction "THERMAL_PAD_17") (pintype "bidirectional"))
    )
    (net (code "109") (name "unconnected-(IC5-PB4-Pad90)") (class "Default")
      (node (ref "IC5") (pin "90") (pinfunction "PB4_90") (pintype "bidirectional"))
    )
    (net (code "110") (name "unconnected-(IC5-PB5-Pad91)") (class "Default")
      (node (ref "IC5") (pin "91") (pinfunction "PB5_91") (pintype "bidirectional"))
    )
    (net (code "111") (name "unconnected-(IC5-PB12-Pad51)") (class "Default")
      (node (ref "IC5") (pin "51") (pinfunction "PB12_51") (pintype "bidirectional"))
    )
    (net (code "112") (name "unconnected-(IC5-PC4-Pad33)") (class "Default")
      (node (ref "IC5") (pin "33") (pinfunction "PC4_33") (pintype "bidirectional"))
    )
    (net (code "113") (name "unconnected-(IC5-PC5-Pad34)") (class "Default")
      (node (ref "IC5") (pin "34") (pinfunction "PC5_34") (pintype "bidirectional"))
    )
    (net (code "114") (name "unconnected-(IC5-PC8-Pad65)") (class "Default")
      (node (ref "IC5") (pin "65") (pinfunction "PC8_65") (pintype "bidirectional"))
    )
    (net (code "115") (name "unconnected-(IC5-PC9-Pad66)") (class "Default")
      (node (ref "IC5") (pin "66") (pinfunction "PC9_66") (pintype "bidirectional"))
    )
    (net (code "116") (name "unconnected-(IC5-PC10-Pad78)") (class "Default")
      (node (ref "IC5") (pin "78") (pinfunction "PC10_78") (pintype "bidirectional"))
    )
    (net (code "117") (name "unconnected-(IC5-PC11-Pad79)") (class "Default")
      (node (ref "IC5") (pin "79") (pinfunction "PC11_79") (pintype "bidirectional"))
    )
    (net (code "118") (name "unconnected-(IC5-PC12-Pad80)") (class "Default")
      (node (ref "IC5") (pin "80") (pinfunction "PC12_80") (pintype "bidirectional"))
    )
    (net (code "119") (name "unconnected-(IC5-PC13-Pad7)") (class "Default")
      (node (ref "IC5") (pin "7") (pinfunction "PC13_7") (pintype "bidirectional"))
    )
    (net (code "120") (name "unconnected-(IC5-PC14-Pad8)") (class "Default")
      (node (ref "IC5") (pin "8") (pinfunction "PC14_8") (pintype "bidirectional"))
    )
    (net (code "121") (name "unconnected-(IC5-PC15-Pad9)") (class "Default")
      (node (ref "IC5") (pin "9") (pinfunction "PC15_9") (pintype "bidirectional"))
    )
    (net (code "122") (name "unconnected-(IC5-PD0-Pad81)") (class "Default")
      (node (ref "IC5") (pin "81") (pinfunction "PD0_81") (pintype "bidirectional"))
    )
    (net (code "123") (name "unconnected-(IC5-PD1-Pad82)") (class "Default")
      (node (ref "IC5") (pin "82") (pinfunction "PD1_82") (pintype "bidirectional"))
    )
    (net (code "124") (name "unconnected-(IC5-PD2-Pad83)") (class "Default")
      (node (ref "IC5") (pin "83") (pinfunction "PD2_83") (pintype "bidirectional"))
    )
    (net (code "125") (name "unconnected-(IC5-PD3-Pad84)") (class "Default")
      (node (ref "IC5") (pin "84") (pinfunction "PD3_84") (pintype "bidirectional"))
    )
    (net (code "126") (name "unconnected-(IC5-PD4-Pad85)") (class "Default")
      (node (ref "IC5") (pin "85") (pinfunction "PD4_85") (pintype "bidirectional"))
    )
    (net (code "127") (name "unconnected-(IC5-PD5-Pad86)") (class "Default")
      (node (ref "IC5") (pin "86") (pinfunction "PD5_86") (pintype "bidirectional"))
    )
    (net (code "128") (name "unconnected-(IC5-PD6-Pad87)") (class "Default")
      (node (ref "IC5") (pin "87") (pinfunction "PD6_87") (pintype "bidirectional"))
    )
    (net (code "129") (name "unconnected-(IC5-PD7-Pad88)") (class "Default")
      (node (ref "IC5") (pin "88") (pinfunction "PD7_88") (pintype "bidirectional"))
    )
    (net (code "130") (name "unconnected-(IC5-PD8-Pad55)") (class "Default")
      (node (ref "IC5") (pin "55") (pinfunction "PD8_55") (pintype "bidirectional"))
    )
    (net (code "131") (name "unconnected-(IC5-PD9-Pad56)") (class "Default")
      (node (ref "IC5") (pin "56") (pinfunction "PD9_56") (pintype "bidirectional"))
    )
    (net (code "132") (name "unconnected-(IC5-PD10-Pad57)") (class "Default")
      (node (ref "IC5") (pin "57") (pinfunction "PD10_57") (pintype "bidirectional"))
    )
    (net (code "133") (name "unconnected-(IC5-PD11-Pad58)") (class "Default")
      (node (ref "IC5") (pin "58") (pinfunction "PD11_58") (pintype "bidirectional"))
    )
    (net (code "134") (name "unconnected-(IC5-PD12-Pad59)") (class "Default")
      (node (ref "IC5") (pin "59") (pinfunction "PD12_59") (pintype "bidirectional"))
    )
    (net (code "135") (name "unconnected-(IC5-PD13-Pad60)") (class "Default")
      (node (ref "IC5") (pin "60") (pinfunction "PD13_60") (pintype "bidirectional"))
    )
    (net (code "136") (name "unconnected-(IC5-PD14-Pad61)") (class "Default")
      (node (ref "IC5") (pin "61") (pinfunction "PD14_61") (pintype "bidirectional"))
    )
    (net (code "137") (name "unconnected-(IC5-PE0-Pad97)") (class "Default")
      (node (ref "IC5") (pin "97") (pinfunction "PE0_97") (pintype "bidirectional"))
    )
    (net (code "138") (name "unconnected-(IC5-PE1-Pad98)") (class "Default")
      (node (ref "IC5") (pin "98") (pinfunction "PE1_98") (pintype "bidirectional"))
    )
    (net (code "139") (name "unconnected-(IC5-PE2-Pad1)") (class "Default")
      (node (ref "IC5") (pin "1") (pinfunction "PE2_1") (pintype "bidirectional"))
    )
    (net (code "140") (name "unconnected-(IC5-PE3-Pad2)") (class "Default")
      (node (ref "IC5") (pin "2") (pinfunction "PE3_2") (pintype "bidirectional"))
    )
    (net (code "141") (name "unconnected-(IC5-PE4-Pad3)") (class "Default")
      (node (ref "IC5") (pin "3") (pinfunction "PE4_3") (pintype "bidirectional"))
    )
    (net (code "142") (name "unconnected-(IC5-PE5-Pad4)") (class "Default")
      (node (ref "IC5") (pin "4") (pinfunction "PE5_4") (pintype "bidirectional"))
    )
    (net (code "143") (name "unconnected-(IC5-PE6-Pad5)") (class "Default")
      (node (ref "IC5") (pin "5") (pinfunction "PE6_5") (pintype "bidirectional"))
    )
    (net (code "144") (name "unconnected-(IC5-PE11-Pad42)") (class "Default")
      (node (ref "IC5") (pin "42") (pinfunction "PE11_42") (pintype "bidirectional"))
    )
    (net (code "145") (name "unconnected-(IC5-PE12-Pad43)") (class "Default")
      (node (ref "IC5") (pin "43") (pinfunction "PE12_43") (pintype "bidirectional"))
    )
    (net (code "146") (name "unconnected-(IC5-PE13-Pad44)") (class "Default")
      (node (ref "IC5") (pin "44") (pinfunction "PE13_44") (pintype "bidirectional"))
    )
    (net (code "147") (name "unconnected-(IC5-PE14-Pad45)") (class "Default")
      (node (ref "IC5") (pin "45") (pinfunction "PE14_45") (pintype "bidirectional"))
    )
    (net (code "148") (name "unconnected-(IC5-PE15-Pad46)") (class "Default")
      (node (ref "IC5") (pin "46") (pinfunction "PE15_46") (pintype "bidirectional"))
    )
    (net (code "149") (name "unconnected-(LEFT_MOTOR-Pad2)") (class "Default")
      (node (ref "LEFT_MOTOR") (pin "2") (pinfunction "2_2") (pintype "bidirectional"))
    )
    (net (code "150") (name "unconnected-(RIGHT_MOTOR-Pad2)") (class "Default")
      (node (ref "RIGHT_MOTOR") (pin "2") (pinfunction "2_2") (pintype "bidirectional"))
    )
    (net (code "151") (name "unconnected-(SPI_CMP-THERMAL_PAD-Pad17)") (class "Default")
      (node (ref "SPI_CMP") (pin "17") (pinfunction "THERMAL_PAD_17") (pintype "bidirectional"))
    )
  )
)
